# ES_Daisy_Field_Rev4.net
KiCad netlist of a schematic drawn in EAGLE
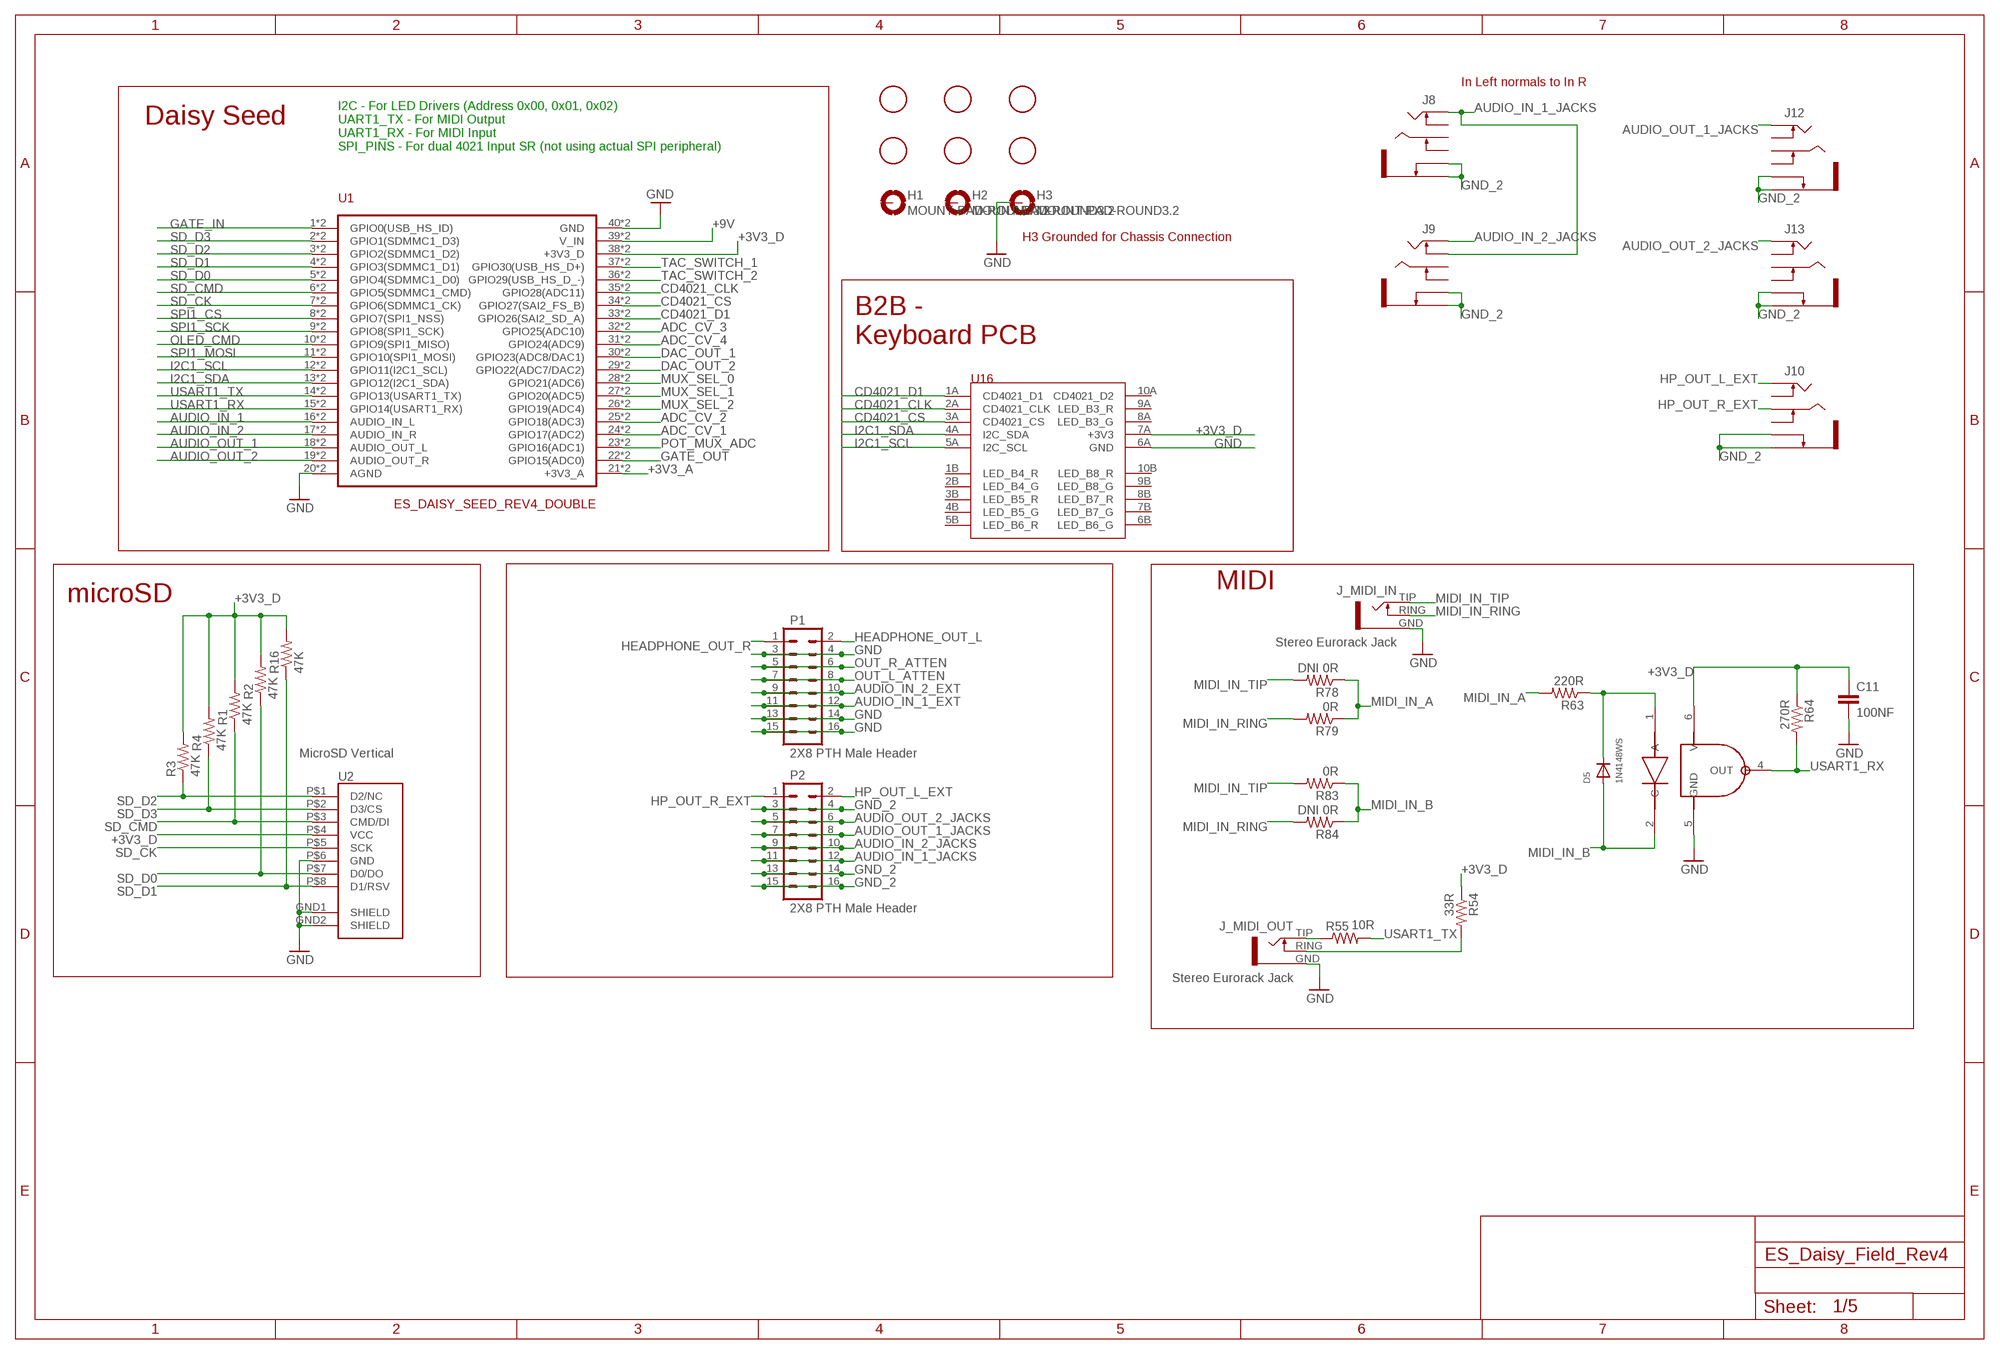
[diagram p0: schematic, sheet 1]
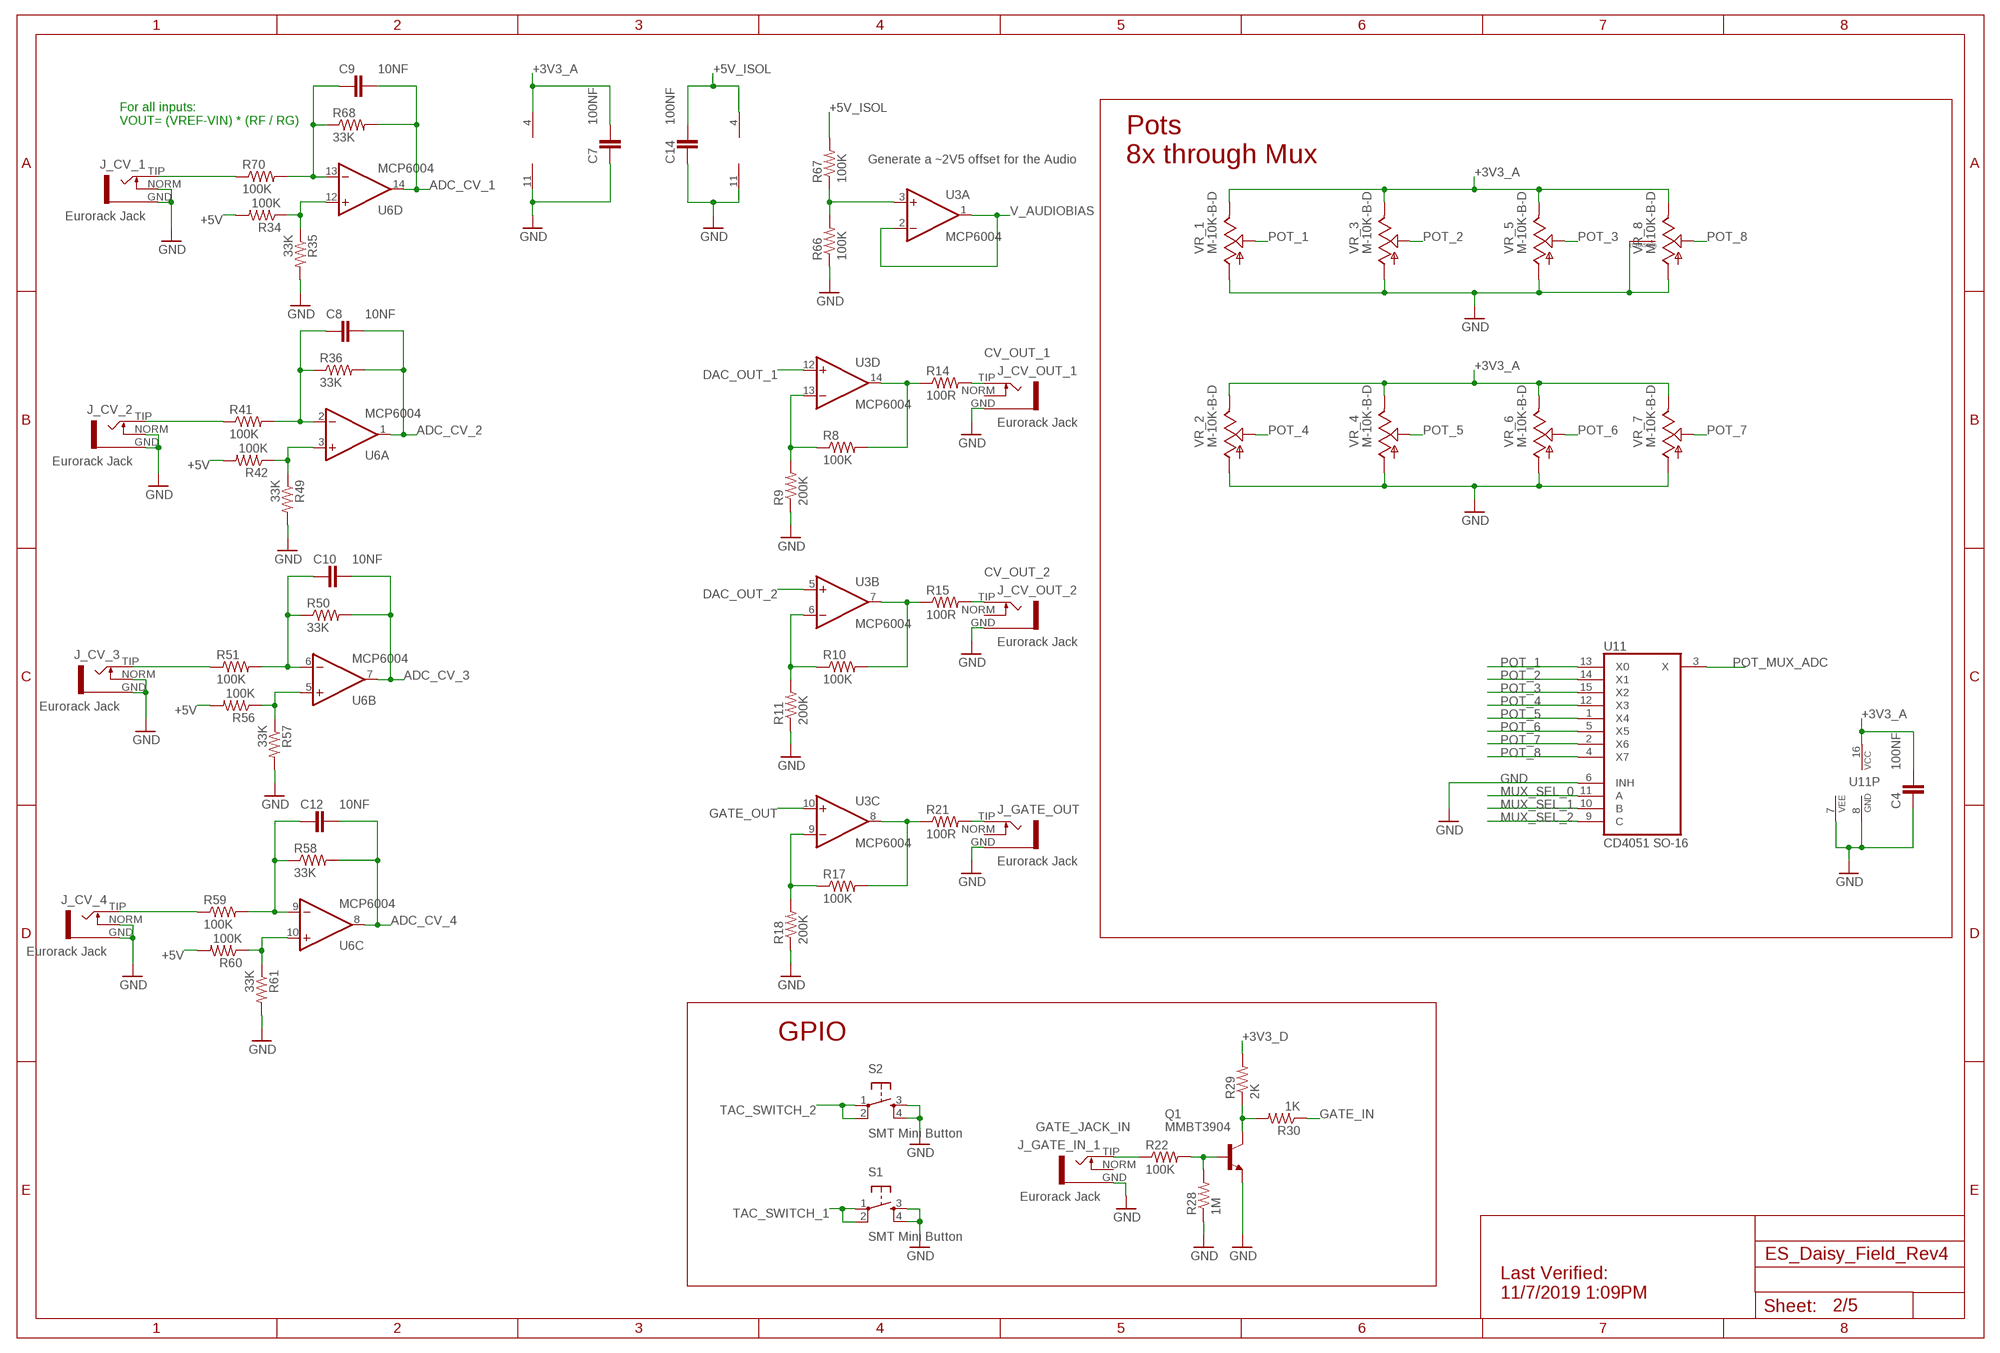
[diagram p1: schematic, sheet 2]
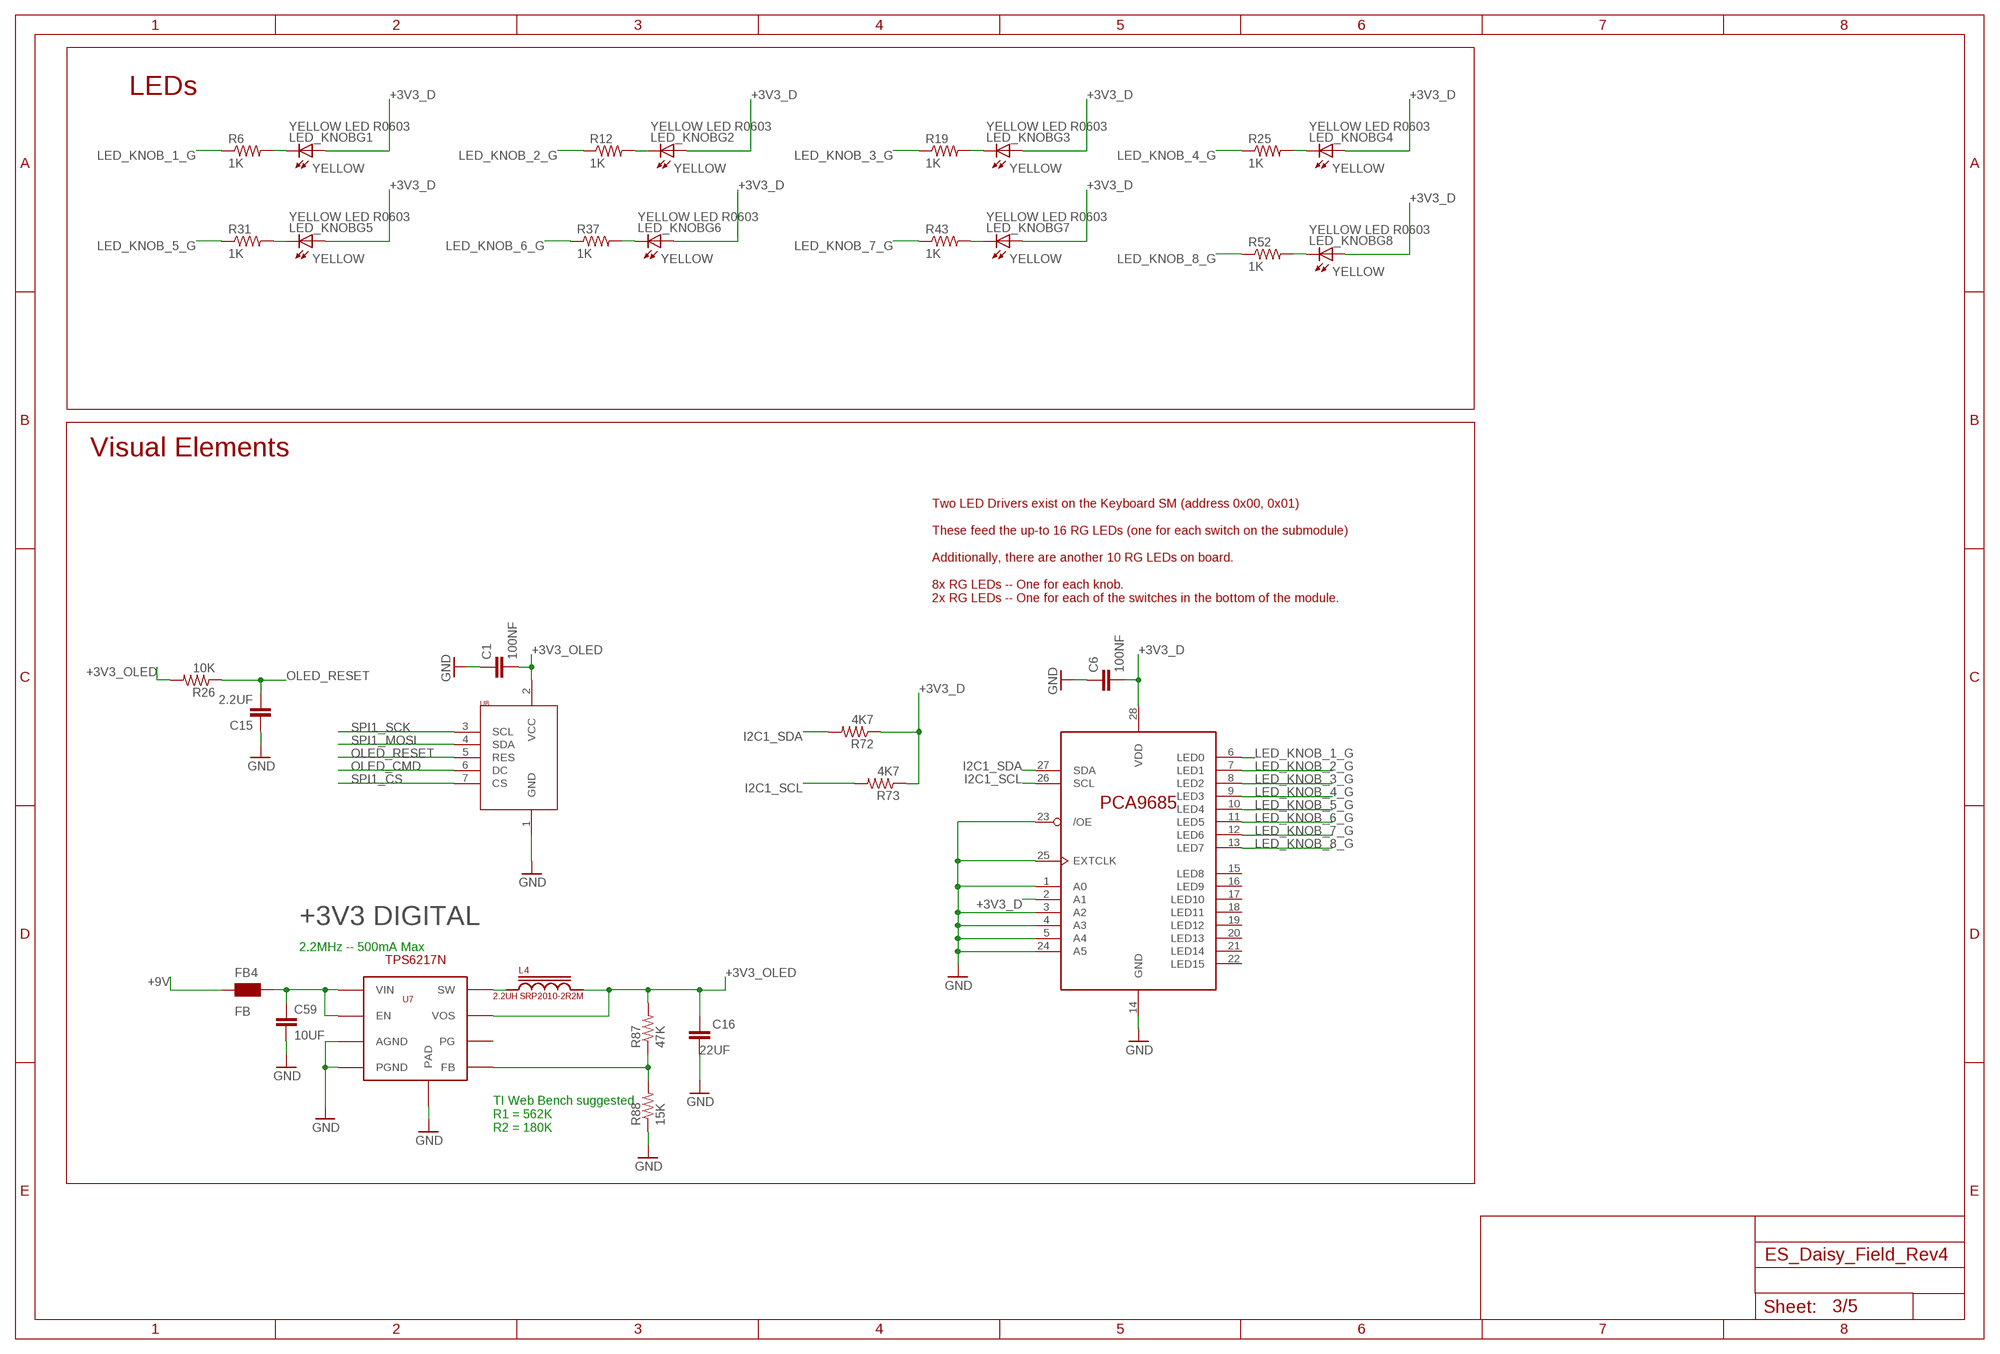
[diagram p2: schematic, sheet 3]
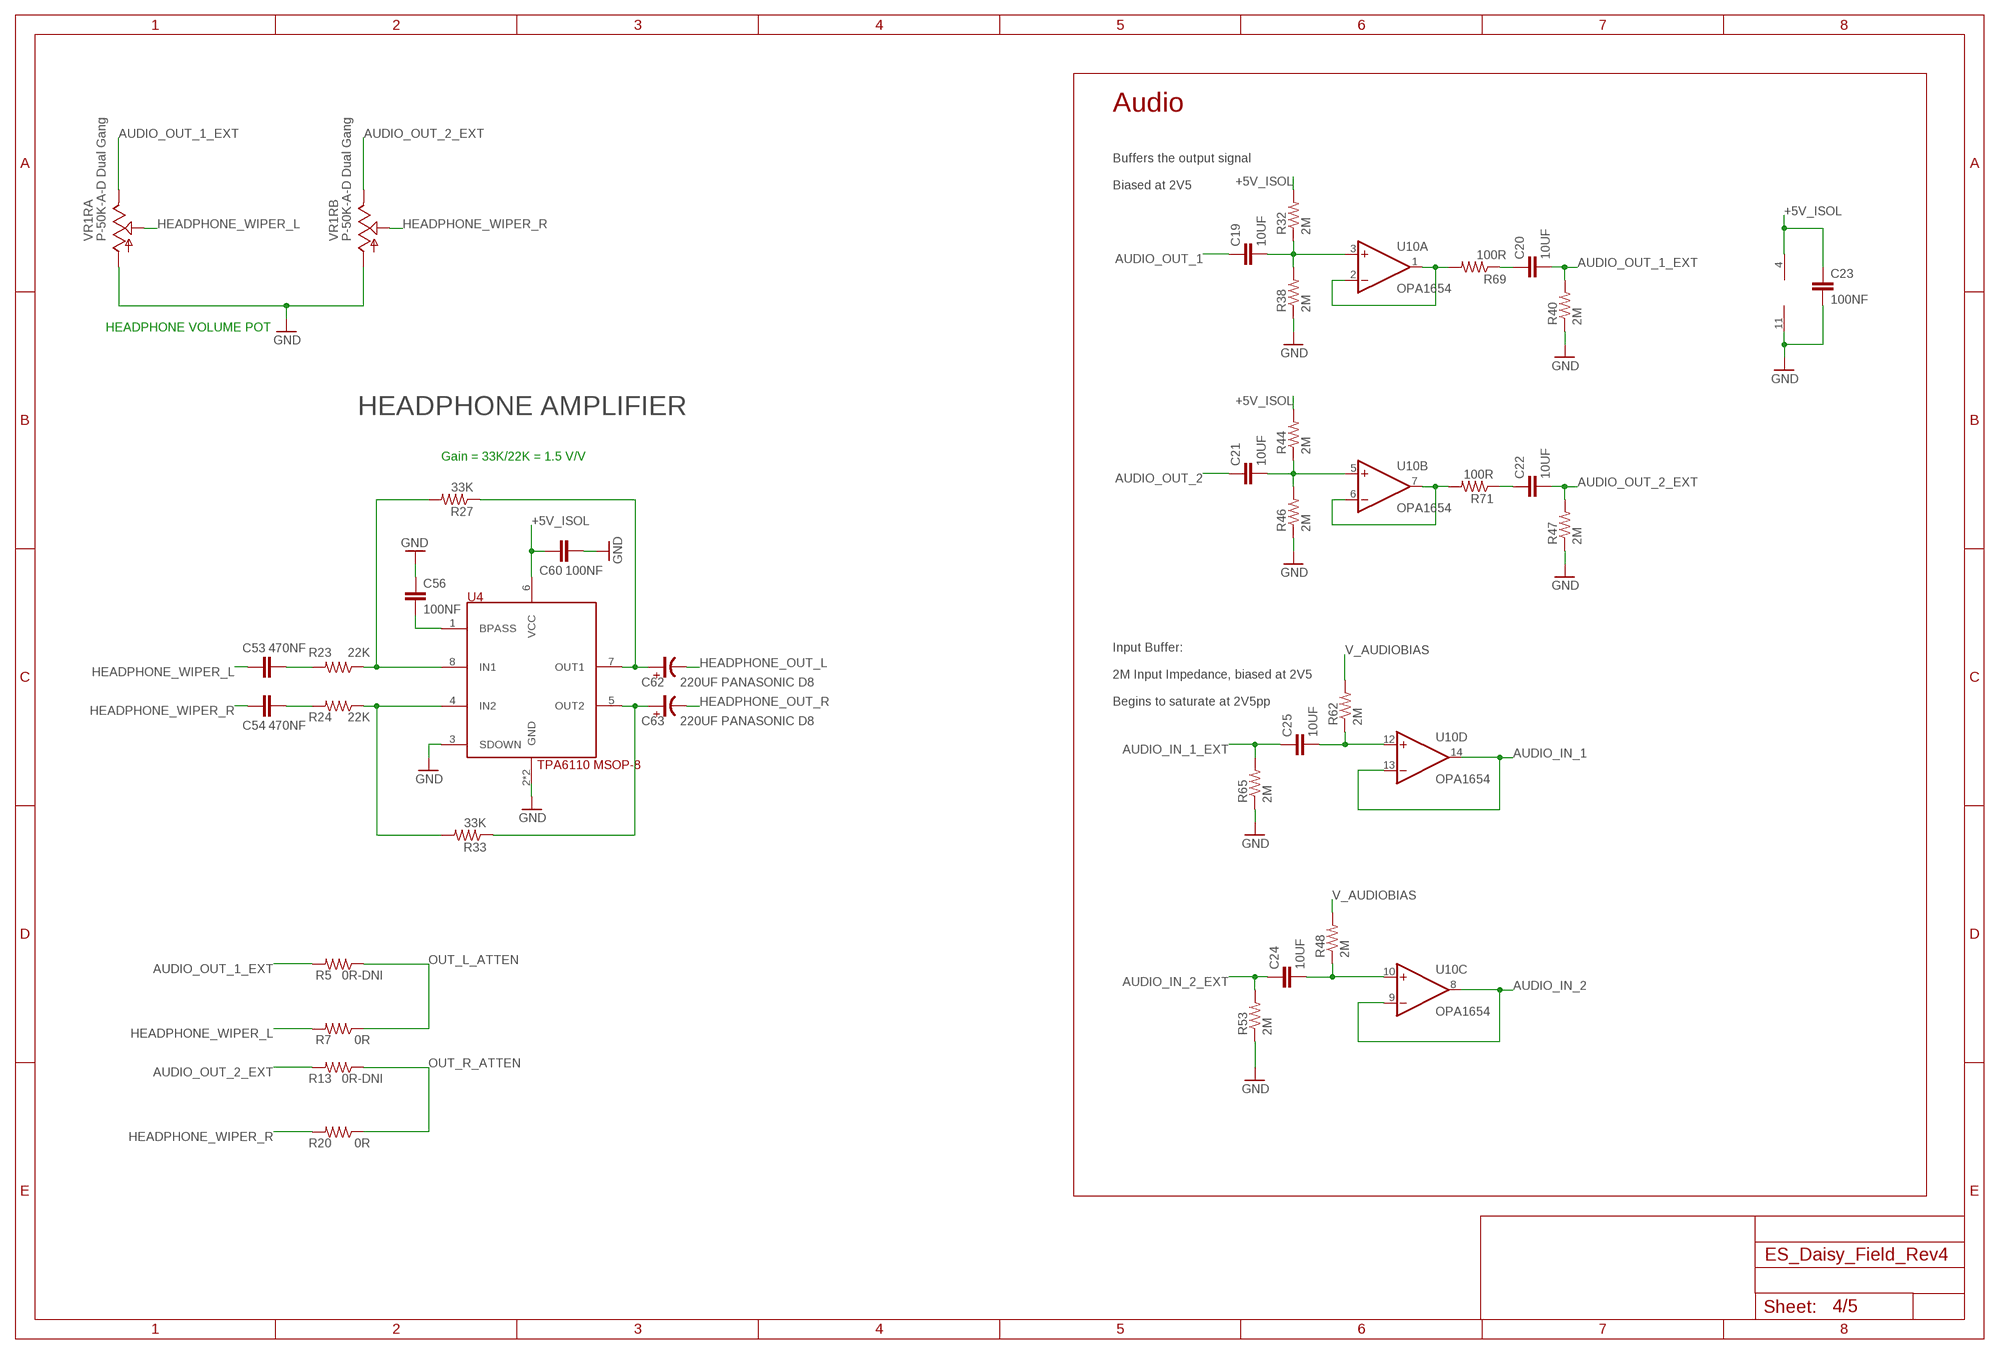
[diagram p3: schematic, sheet 4]
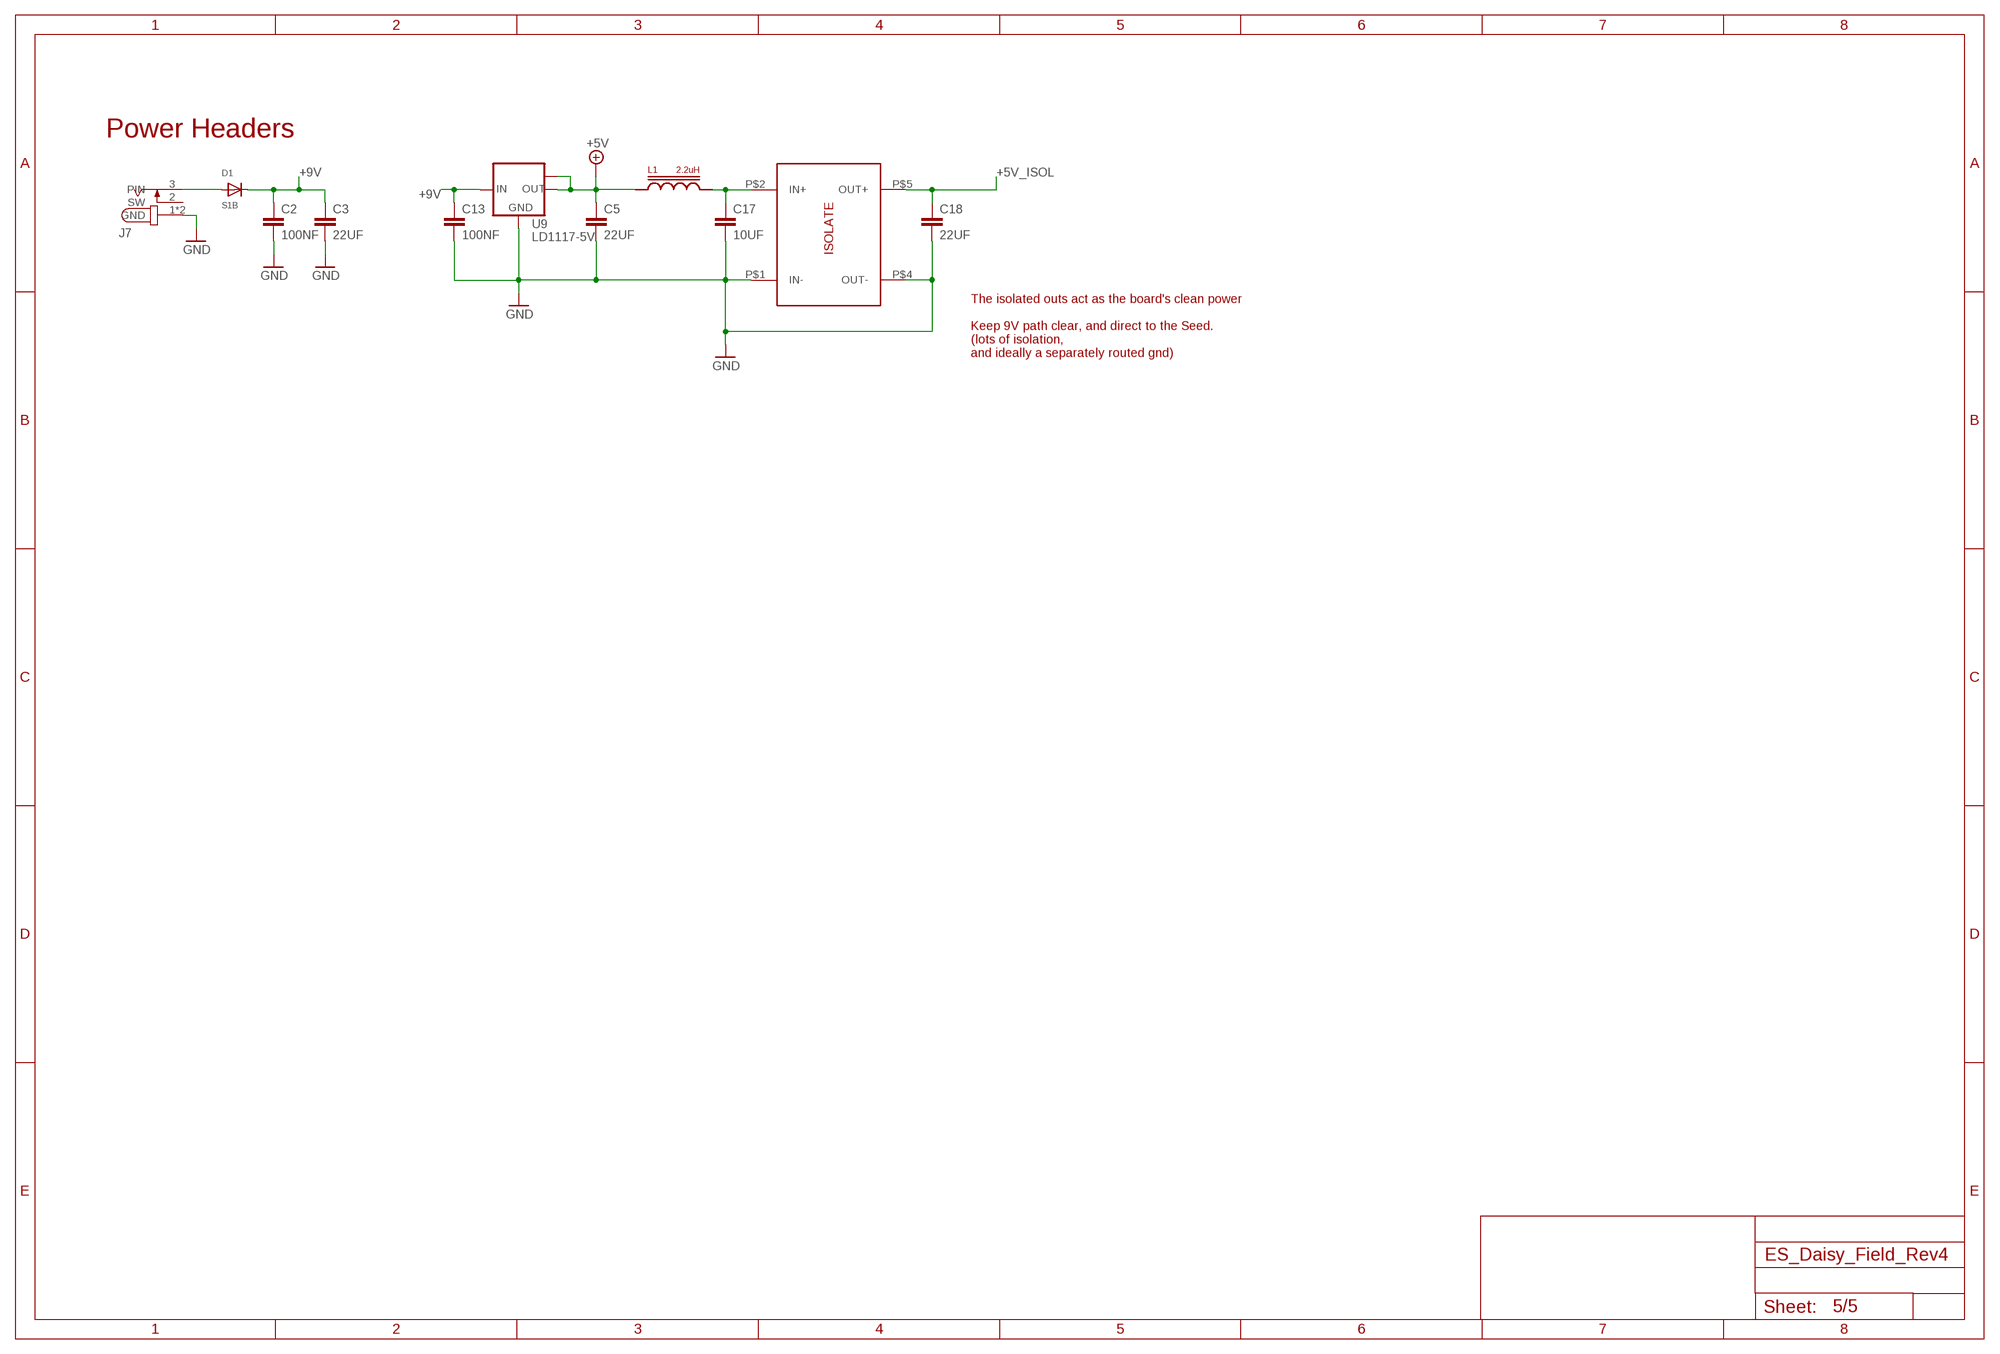
[diagram p4: schematic, sheet 5]

(export (version "E")
  (design (tool "Eeschema 10.0.6"))
  (components
    (comp (ref "C11")
      (value "100NF")
      (footprint "eagle-import:C0603")
      (libsource (lib "eagle-import") (part "C-EUC0603"))
    )
    (comp (ref "D5")
      (value "1N4148WS")
      (footprint "eagle-import:SOD-323F")
      (libsource (lib "eagle-import") (part "DIODE_SOD-323F"))
    )
    (comp (ref "FD1")
      (value "FIDUCIAL")
      (footprint "eagle-import:FIDUCIAL_1MM")
      (libsource (lib "eagle-import") (part "FIDUCIAL"))
    )
    (comp (ref "FD2")
      (value "FIDUCIAL")
      (footprint "eagle-import:FIDUCIAL_1MM")
      (libsource (lib "eagle-import") (part "FIDUCIAL"))
    )
    (comp (ref "FD3")
      (value "FIDUCIAL")
      (footprint "eagle-import:FIDUCIAL_1MM")
      (libsource (lib "eagle-import") (part "FIDUCIAL"))
    )
    (comp (ref "FD4")
      (value "FIDUCIAL")
      (footprint "eagle-import:FIDUCIAL_1MM")
      (libsource (lib "eagle-import") (part "FIDUCIAL"))
    )
    (comp (ref "FD5")
      (value "FIDUCIAL")
      (footprint "eagle-import:FIDUCIAL_1MM")
      (libsource (lib "eagle-import") (part "FIDUCIAL"))
    )
    (comp (ref "FD6")
      (value "FIDUCIAL")
      (footprint "eagle-import:FIDUCIAL_1MM")
      (libsource (lib "eagle-import") (part "FIDUCIAL"))
    )
    (comp (ref "H1")
      (value "MOUNT-PAD-ROUND3.2")
      (footprint "eagle-import:32-PAD")
      (libsource (lib "eagle-import") (part "MOUNT-PAD-ROUND3.2"))
    )
    (comp (ref "H2")
      (value "MOUNT-PAD-ROUND3.2")
      (footprint "eagle-import:32-PAD")
      (libsource (lib "eagle-import") (part "MOUNT-PAD-ROUND3.2"))
    )
    (comp (ref "H3")
      (value "MOUNT-PAD-ROUND3.2")
      (footprint "eagle-import:32-PAD")
      (libsource (lib "eagle-import") (part "MOUNT-PAD-ROUND3.2"))
    )
    (comp (ref "J8")
      (value "PTH Switching Stereo Guitar Jack")
      (footprint "eagle-import:WQP-PJ6110")
      (libsource (lib "eagle-import") (part "JACK_TRS_SWITCHING_WQP-PJ6110"))
    )
    (comp (ref "J9")
      (value "PTH Switching Stereo Guitar Jack")
      (footprint "eagle-import:WQP-PJ6110")
      (libsource (lib "eagle-import") (part "JACK_TRS_SWITCHING_WQP-PJ6110"))
    )
    (comp (ref "J10")
      (value "PTH Switching Stereo Guitar Jack")
      (footprint "eagle-import:WQP-PJ6110")
      (libsource (lib "eagle-import") (part "JACK_TRS_SWITCHING_WQP-PJ6110"))
    )
    (comp (ref "J12")
      (value "PTH Switching Stereo Guitar Jack")
      (footprint "eagle-import:WQP-PJ6110")
      (libsource (lib "eagle-import") (part "JACK_TRS_SWITCHING_WQP-PJ6110"))
    )
    (comp (ref "J13")
      (value "PTH Switching Stereo Guitar Jack")
      (footprint "eagle-import:WQP-PJ6110")
      (libsource (lib "eagle-import") (part "JACK_TRS_SWITCHING_WQP-PJ6110"))
    )
    (comp (ref "J_MIDI_IN")
      (value "Stereo Eurorack Jack")
      (footprint "eagle-import:STEREO_JACK_3.5MM")
      (libsource (lib "eagle-import") (part "STEREO_JACK"))
    )
    (comp (ref "J_MIDI_OUT")
      (value "Stereo Eurorack Jack")
      (footprint "eagle-import:STEREO_JACK_3.5MM")
      (libsource (lib "eagle-import") (part "STEREO_JACK"))
    )
    (comp (ref "P1")
      (value "2X8 PTH Male Header")
      (footprint "eagle-import:2X8_LOCK")
      (libsource (lib "eagle-import") (part "M08X2?_LOCK_SILK"))
    )
    (comp (ref "P2")
      (value "2X8 PTH Male Header")
      (footprint "eagle-import:2X8_LOCK")
      (libsource (lib "eagle-import") (part "M08X2?_LOCK_SILK"))
    )
    (comp (ref "R1")
      (value "47K")
      (footprint "eagle-import:R0603")
      (libsource (lib "eagle-import") (part "R-US_R0603"))
    )
    (comp (ref "R2")
      (value "47K")
      (footprint "eagle-import:R0603")
      (libsource (lib "eagle-import") (part "R-US_R0603"))
    )
    (comp (ref "R3")
      (value "47K")
      (footprint "eagle-import:R0603")
      (libsource (lib "eagle-import") (part "R-US_R0603"))
    )
    (comp (ref "R4")
      (value "47K")
      (footprint "eagle-import:R0603")
      (libsource (lib "eagle-import") (part "R-US_R0603"))
    )
    (comp (ref "R16")
      (value "47K")
      (footprint "eagle-import:R0603")
      (libsource (lib "eagle-import") (part "R-US_R0603"))
    )
    (comp (ref "R54")
      (value "33R")
      (footprint "eagle-import:R0603")
      (libsource (lib "eagle-import") (part "R-US_R0603"))
    )
    (comp (ref "R55")
      (value "10R")
      (footprint "eagle-import:R0603")
      (libsource (lib "eagle-import") (part "R-US_R0603"))
    )
    (comp (ref "R63")
      (value "220R")
      (footprint "eagle-import:R0603")
      (libsource (lib "eagle-import") (part "R-US_R0603"))
    )
    (comp (ref "R64")
      (value "270R")
      (footprint "eagle-import:R0603")
      (libsource (lib "eagle-import") (part "R-US_R0603"))
    )
    (comp (ref "R78")
      (value "DNI 0R")
      (footprint "eagle-import:R0603")
      (libsource (lib "eagle-import") (part "R-US_R0603"))
    )
    (comp (ref "R79")
      (value "0R")
      (footprint "eagle-import:R0603")
      (libsource (lib "eagle-import") (part "R-US_R0603"))
    )
    (comp (ref "R83")
      (value "0R")
      (footprint "eagle-import:R0603")
      (libsource (lib "eagle-import") (part "R-US_R0603"))
    )
    (comp (ref "R84")
      (value "DNI 0R")
      (footprint "eagle-import:R0603")
      (libsource (lib "eagle-import") (part "R-US_R0603"))
    )
    (comp (ref "U1")
      (value "ES_DAISY_SEED_REV4_DOUBLE")
      (footprint "eagle-import:ES_DAISY_SEED_DOUBLE")
      (libsource (lib "eagle-import") (part "ES_DAISY_SEED_REV4_DOUBLE"))
    )
    (comp (ref "U2")
      (value "MicroSD Vertical")
      (footprint "eagle-import:VERT_MICROSD_CENTERED")
      (libsource (lib "eagle-import") (part "MICRO_SD_CARDCENTERED"))
    )
    (comp (ref "U15")
      (value "OPTO ISOLATOR")
      (footprint "eagle-import:DIL06_GULLWING")
      (fields (field (name "MPN") "H11L1SR2M"))
      (libsource (lib "eagle-import") (part "OPTOISOLATOR_H11L1M"))
    )
    (comp (ref "U16")
      (value "ES_KEYBOARD_SM_REV2_ALIGNED")
      (footprint "eagle-import:ES_KEYBOARD_SM_REV2_ALIGNED")
      (libsource (lib "eagle-import") (part "ES_KEYBOARD_SM_REV2_ALIGNED"))
    )
    (comp (ref "C1")
      (value "100NF")
      (footprint "eagle-import:C0603")
      (libsource (lib "eagle-import") (part "C-EUC0603"))
    )
    (comp (ref "C6")
      (value "100NF")
      (footprint "eagle-import:C0603")
      (libsource (lib "eagle-import") (part "C-EUC0603"))
    )
    (comp (ref "C15")
      (value "2.2UF")
      (footprint "eagle-import:C0603")
      (libsource (lib "eagle-import") (part "C-EUC0603"))
    )
    (comp (ref "C16")
      (value "22UF")
      (footprint "eagle-import:C1206")
      (libsource (lib "eagle-import") (part "C-EUC1206"))
    )
    (comp (ref "C59")
      (value "10UF")
      (footprint "eagle-import:C0805")
      (libsource (lib "eagle-import") (part "C-EUC0805"))
    )
    (comp (ref "FB4")
      (value "FB")
      (footprint "eagle-import:WUERTH-ELEKTRONIK_0603")
      (fields (field (name "MPN") "MI0603J601R-10"))
      (libsource (lib "eagle-import") (part "FERRITE_BEAD_0603"))
    )
    (comp (ref "L4")
      (value "2.2UH SRP2010-2R2M")
      (footprint "eagle-import:BOURNS_SRP2010")
      (libsource (lib "eagle-import") (part "INDUCTORS"))
    )
    (comp (ref "LED_KNOBG1")
      (value "YELLOW LED R0603")
      (footprint "eagle-import:DIODE_0603")
      (fields (field (name "COLOR") "YELLOW") (field (name "MPN") "APT1608LSYCK/J3-PRV"))
      (libsource (lib "eagle-import") (part "LED_0603_YELLOW"))
    )
    (comp (ref "LED_KNOBG2")
      (value "YELLOW LED R0603")
      (footprint "eagle-import:DIODE_0603")
      (fields (field (name "COLOR") "YELLOW") (field (name "MPN") "APT1608LSYCK/J3-PRV"))
      (libsource (lib "eagle-import") (part "LED_0603_YELLOW"))
    )
    (comp (ref "LED_KNOBG3")
      (value "YELLOW LED R0603")
      (footprint "eagle-import:DIODE_0603")
      (fields (field (name "COLOR") "YELLOW") (field (name "MPN") "APT1608LSYCK/J3-PRV"))
      (libsource (lib "eagle-import") (part "LED_0603_YELLOW"))
    )
    (comp (ref "LED_KNOBG4")
      (value "YELLOW LED R0603")
      (footprint "eagle-import:DIODE_0603")
      (fields (field (name "COLOR") "YELLOW") (field (name "MPN") "APT1608LSYCK/J3-PRV"))
      (libsource (lib "eagle-import") (part "LED_0603_YELLOW"))
    )
    (comp (ref "LED_KNOBG5")
      (value "YELLOW LED R0603")
      (footprint "eagle-import:DIODE_0603")
      (fields (field (name "COLOR") "YELLOW") (field (name "MPN") "APT1608LSYCK/J3-PRV"))
      (libsource (lib "eagle-import") (part "LED_0603_YELLOW"))
    )
    (comp (ref "LED_KNOBG6")
      (value "YELLOW LED R0603")
      (footprint "eagle-import:DIODE_0603")
      (fields (field (name "COLOR") "YELLOW") (field (name "MPN") "APT1608LSYCK/J3-PRV"))
      (libsource (lib "eagle-import") (part "LED_0603_YELLOW"))
    )
    (comp (ref "LED_KNOBG7")
      (value "YELLOW LED R0603")
      (footprint "eagle-import:DIODE_0603")
      (fields (field (name "COLOR") "YELLOW") (field (name "MPN") "APT1608LSYCK/J3-PRV"))
      (libsource (lib "eagle-import") (part "LED_0603_YELLOW"))
    )
    (comp (ref "LED_KNOBG8")
      (value "YELLOW LED R0603")
      (footprint "eagle-import:DIODE_0603")
      (fields (field (name "COLOR") "YELLOW") (field (name "MPN") "APT1608LSYCK/J3-PRV"))
      (libsource (lib "eagle-import") (part "LED_0603_YELLOW"))
    )
    (comp (ref "R6")
      (value "1K")
      (footprint "eagle-import:R0603")
      (libsource (lib "eagle-import") (part "R-US_R0603"))
    )
    (comp (ref "R12")
      (value "1K")
      (footprint "eagle-import:R0603")
      (libsource (lib "eagle-import") (part "R-US_R0603"))
    )
    (comp (ref "R19")
      (value "1K")
      (footprint "eagle-import:R0603")
      (libsource (lib "eagle-import") (part "R-US_R0603"))
    )
    (comp (ref "R25")
      (value "1K")
      (footprint "eagle-import:R0603")
      (libsource (lib "eagle-import") (part "R-US_R0603"))
    )
    (comp (ref "R26")
      (value "10K")
      (footprint "eagle-import:R0603")
      (libsource (lib "eagle-import") (part "R-US_R0603"))
    )
    (comp (ref "R31")
      (value "1K")
      (footprint "eagle-import:R0603")
      (libsource (lib "eagle-import") (part "R-US_R0603"))
    )
    (comp (ref "R37")
      (value "1K")
      (footprint "eagle-import:R0603")
      (libsource (lib "eagle-import") (part "R-US_R0603"))
    )
    (comp (ref "R43")
      (value "1K")
      (footprint "eagle-import:R0603")
      (libsource (lib "eagle-import") (part "R-US_R0603"))
    )
    (comp (ref "R52")
      (value "1K")
      (footprint "eagle-import:R0603")
      (libsource (lib "eagle-import") (part "R-US_R0603"))
    )
    (comp (ref "R72")
      (value "4K7")
      (footprint "eagle-import:R0603")
      (libsource (lib "eagle-import") (part "R-US_R0603"))
    )
    (comp (ref "R73")
      (value "4K7")
      (footprint "eagle-import:R0603")
      (libsource (lib "eagle-import") (part "R-US_R0603"))
    )
    (comp (ref "R87")
      (value "47K")
      (footprint "eagle-import:R0603")
      (libsource (lib "eagle-import") (part "R-US_R0603"))
    )
    (comp (ref "R88")
      (value "15K")
      (footprint "eagle-import:R0603")
      (libsource (lib "eagle-import") (part "R-US_R0603"))
    )
    (comp (ref "U5")
      (value "PCA9685 TSSOP-28")
      (footprint "eagle-import:TSSOP-28")
      (fields (field (name "MPN") "PCA9685PW,118"))
      (libsource (lib "eagle-import") (part "PCA9685PW"))
    )
    (comp (ref "U7")
      (value "TPS62170 WSON-8")
      (footprint "eagle-import:WSON-8")
      (fields (field (name "MPN") "TPS62170"))
      (libsource (lib "eagle-import") (part "TPS6217N"))
    )
    (comp (ref "U8")
      (value "OLED_DISPLAY")
      (footprint "eagle-import:ER-OLEDM015-2")
      (fields (field (name "MPN") "ER-OLEDM015-2W-SPI-I2C"))
      (libsource (lib "eagle-import") (part "OLED_DISPLAY"))
    )
    (comp (ref "C2")
      (value "100NF")
      (footprint "eagle-import:C0603")
      (libsource (lib "eagle-import") (part "C-EUC0603"))
    )
    (comp (ref "C3")
      (value "22UF")
      (footprint "eagle-import:C1206")
      (libsource (lib "eagle-import") (part "C-EUC1206"))
    )
    (comp (ref "C5")
      (value "22UF")
      (footprint "eagle-import:C0805")
      (libsource (lib "eagle-import") (part "C-EUC0805"))
    )
    (comp (ref "C13")
      (value "100NF")
      (footprint "eagle-import:C0603")
      (libsource (lib "eagle-import") (part "C-EUC0603"))
    )
    (comp (ref "C17")
      (value "10UF")
      (footprint "eagle-import:C0805")
      (libsource (lib "eagle-import") (part "C-EUC0805"))
    )
    (comp (ref "C18")
      (value "22UF")
      (footprint "eagle-import:C1206")
      (libsource (lib "eagle-import") (part "C-EUC1206"))
    )
    (comp (ref "D1")
      (value "S1B")
      (footprint "eagle-import:SMADIODE")
      (libsource (lib "eagle-import") (part "S1B"))
    )
    (comp (ref "J7")
      (value "SMT GUITAR DC JACK")
      (footprint "eagle-import:WQP-DC0500")
      (libsource (lib "eagle-import") (part "GUITAR_DC_JACK"))
    )
    (comp (ref "L1")
      (value "2.2uH")
      (footprint "eagle-import:BOURNS_SRP2010")
      (libsource (lib "eagle-import") (part "INDUCTORS"))
    )
    (comp (ref "U$4")
      (value "POWER_ISOLATE")
      (footprint "eagle-import:XP_POWER_ISEXXXXA")
      (fields (field (name "MPN") "ISE2405A"))
      (libsource (lib "eagle-import") (part "POWER_ISOLATE"))
    )
    (comp (ref "U9")
      (value "LD1117-5V")
      (footprint "eagle-import:SOT223")
      (fields (field (name "MPN") "LD1117S50CTR"))
      (libsource (lib "eagle-import") (part "LD1117-5V"))
    )
    (comp (ref "C19")
      (value "10UF")
      (footprint "eagle-import:C0805")
      (libsource (lib "eagle-import") (part "C-EUC0805"))
    )
    (comp (ref "C20")
      (value "10UF")
      (footprint "eagle-import:C0805")
      (libsource (lib "eagle-import") (part "C-EUC0805"))
    )
    (comp (ref "C21")
      (value "10UF")
      (footprint "eagle-import:C0805")
      (libsource (lib "eagle-import") (part "C-EUC0805"))
    )
    (comp (ref "C22")
      (value "10UF")
      (footprint "eagle-import:C0805")
      (libsource (lib "eagle-import") (part "C-EUC0805"))
    )
    (comp (ref "C23")
      (value "100NF")
      (footprint "eagle-import:C0603")
      (libsource (lib "eagle-import") (part "C-EUC0603"))
    )
    (comp (ref "C24")
      (value "10UF")
      (footprint "eagle-import:C0805")
      (libsource (lib "eagle-import") (part "C-EUC0805"))
    )
    (comp (ref "C25")
      (value "10UF")
      (footprint "eagle-import:C0805")
      (libsource (lib "eagle-import") (part "C-EUC0805"))
    )
    (comp (ref "C53")
      (value "470NF")
      (footprint "eagle-import:C0603")
      (libsource (lib "eagle-import") (part "C-EUC0603"))
    )
    (comp (ref "C54")
      (value "470NF")
      (footprint "eagle-import:C0603")
      (libsource (lib "eagle-import") (part "C-EUC0603"))
    )
    (comp (ref "C56")
      (value "100NF")
      (footprint "eagle-import:C0603")
      (libsource (lib "eagle-import") (part "C-EUC0603"))
    )
    (comp (ref "C60")
      (value "100NF")
      (footprint "eagle-import:C0603")
      (libsource (lib "eagle-import") (part "C-EUC0603"))
    )
    (comp (ref "C62")
      (value "220UF PANASONIC D8")
      (footprint "eagle-import:PANASONIC_D")
      (libsource (lib "eagle-import") (part "C-EU-POL_D"))
    )
    (comp (ref "C63")
      (value "220UF PANASONIC D8")
      (footprint "eagle-import:PANASONIC_D")
      (libsource (lib "eagle-import") (part "C-EU-POL_D"))
    )
    (comp (ref "R5")
      (value "0R-DNI")
      (footprint "eagle-import:R0603")
      (libsource (lib "eagle-import") (part "R-US_R0603"))
    )
    (comp (ref "R7")
      (value "0R")
      (footprint "eagle-import:R0603")
      (libsource (lib "eagle-import") (part "R-US_R0603"))
    )
    (comp (ref "R13")
      (value "0R-DNI")
      (footprint "eagle-import:R0603")
      (libsource (lib "eagle-import") (part "R-US_R0603"))
    )
    (comp (ref "R20")
      (value "0R")
      (footprint "eagle-import:R0603")
      (libsource (lib "eagle-import") (part "R-US_R0603"))
    )
    (comp (ref "R23")
      (value "22K")
      (footprint "eagle-import:R0603")
      (libsource (lib "eagle-import") (part "R-US_R0603"))
    )
    (comp (ref "R24")
      (value "22K")
      (footprint "eagle-import:R0603")
      (libsource (lib "eagle-import") (part "R-US_R0603"))
    )
    (comp (ref "R27")
      (value "33K")
      (footprint "eagle-import:R0603")
      (libsource (lib "eagle-import") (part "R-US_R0603"))
    )
    (comp (ref "R32")
      (value "2M")
      (footprint "eagle-import:R0603")
      (libsource (lib "eagle-import") (part "R-US_R0603"))
    )
    (comp (ref "R33")
      (value "33K")
      (footprint "eagle-import:R0603")
      (libsource (lib "eagle-import") (part "R-US_R0603"))
    )
    (comp (ref "R38")
      (value "2M")
      (footprint "eagle-import:R0603")
      (libsource (lib "eagle-import") (part "R-US_R0603"))
    )
    (comp (ref "R40")
      (value "2M")
      (footprint "eagle-import:R0603")
      (libsource (lib "eagle-import") (part "R-US_R0603"))
    )
    (comp (ref "R44")
      (value "2M")
      (footprint "eagle-import:R0603")
      (libsource (lib "eagle-import") (part "R-US_R0603"))
    )
    (comp (ref "R46")
      (value "2M")
      (footprint "eagle-import:R0603")
      (libsource (lib "eagle-import") (part "R-US_R0603"))
    )
    (comp (ref "R47")
      (value "2M")
      (footprint "eagle-import:R0603")
      (libsource (lib "eagle-import") (part "R-US_R0603"))
    )
    (comp (ref "R48")
      (value "2M")
      (footprint "eagle-import:R0603")
      (libsource (lib "eagle-import") (part "R-US_R0603"))
    )
    (comp (ref "R53")
      (value "2M")
      (footprint "eagle-import:R0603")
      (libsource (lib "eagle-import") (part "R-US_R0603"))
    )
    (comp (ref "R62")
      (value "2M")
      (footprint "eagle-import:R0603")
      (libsource (lib "eagle-import") (part "R-US_R0603"))
    )
    (comp (ref "R65")
      (value "2M")
      (footprint "eagle-import:R0603")
      (libsource (lib "eagle-import") (part "R-US_R0603"))
    )
    (comp (ref "R69")
      (value "100R")
      (footprint "eagle-import:R0603")
      (libsource (lib "eagle-import") (part "R-US_R0603"))
    )
    (comp (ref "R71")
      (value "100R")
      (footprint "eagle-import:R0603")
      (libsource (lib "eagle-import") (part "R-US_R0603"))
    )
    (comp (ref "U4")
      (value "TPA6110 MSOP-8")
      (footprint "eagle-import:MSOP_8_PWRPAD")
      (libsource (lib "eagle-import") (part "TPA6110MSOP"))
    )
    (comp (ref "U10")
      (value "OPA1654")
      (footprint "eagle-import:TSSOP-14")
      (libsource (lib "eagle-import") (part "OPA1654_TSSOP-14"))
    )
    (comp (ref "VR1")
      (value "P-50K-A-D Dual Gang")
      (footprint "eagle-import:BOURNS_PTV112_SILK")
      (libsource (lib "eagle-import") (part "POT_DUAL_GANG"))
    )
    (comp (ref "C4")
      (value "100NF")
      (footprint "eagle-import:C0603")
      (libsource (lib "eagle-import") (part "C-EUC0603"))
    )
    (comp (ref "C7")
      (value "100NF")
      (footprint "eagle-import:C0603")
      (libsource (lib "eagle-import") (part "C-EUC0603"))
    )
    (comp (ref "C8")
      (value "10NF")
      (footprint "eagle-import:C0603")
      (libsource (lib "eagle-import") (part "C-EUC0603"))
    )
    (comp (ref "C9")
      (value "10NF")
      (footprint "eagle-import:C0603")
      (libsource (lib "eagle-import") (part "C-EUC0603"))
    )
    (comp (ref "C10")
      (value "10NF")
      (footprint "eagle-import:C0603")
      (libsource (lib "eagle-import") (part "C-EUC0603"))
    )
    (comp (ref "C12")
      (value "10NF")
      (footprint "eagle-import:C0603")
      (libsource (lib "eagle-import") (part "C-EUC0603"))
    )
    (comp (ref "C14")
      (value "100NF")
      (footprint "eagle-import:C0603")
      (libsource (lib "eagle-import") (part "C-EUC0603"))
    )
    (comp (ref "J_CV_1")
      (value "Eurorack Jack")
      (footprint "eagle-import:S_JACK")
      (libsource (lib "eagle-import") (part "EURO_JACK"))
    )
    (comp (ref "J_CV_2")
      (value "Eurorack Jack")
      (footprint "eagle-import:S_JACK")
      (libsource (lib "eagle-import") (part "EURO_JACK"))
    )
    (comp (ref "J_CV_3")
      (value "Eurorack Jack")
      (footprint "eagle-import:S_JACK")
      (libsource (lib "eagle-import") (part "EURO_JACK"))
    )
    (comp (ref "J_CV_4")
      (value "Eurorack Jack")
      (footprint "eagle-import:S_JACK")
      (libsource (lib "eagle-import") (part "EURO_JACK"))
    )
    (comp (ref "J_CV_OUT_1")
      (value "Eurorack Jack")
      (footprint "eagle-import:S_JACK")
      (libsource (lib "eagle-import") (part "EURO_JACK"))
    )
    (comp (ref "J_CV_OUT_2")
      (value "Eurorack Jack")
      (footprint "eagle-import:S_JACK")
      (libsource (lib "eagle-import") (part "EURO_JACK"))
    )
    (comp (ref "J_GATE_IN_1")
      (value "Eurorack Jack")
      (footprint "eagle-import:S_JACK")
      (libsource (lib "eagle-import") (part "EURO_JACK"))
    )
    (comp (ref "J_GATE_OUT")
      (value "Eurorack Jack")
      (footprint "eagle-import:S_JACK")
      (libsource (lib "eagle-import") (part "EURO_JACK"))
    )
    (comp (ref "Q1")
      (value "MMBT3904")
      (footprint "eagle-import:SOT23-BEC")
      (libsource (lib "eagle-import") (part "NPNSOT23-BEC"))
    )
    (comp (ref "R8")
      (value "100K")
      (footprint "eagle-import:R0603")
      (libsource (lib "eagle-import") (part "R-US_R0603"))
    )
    (comp (ref "R9")
      (value "200K")
      (footprint "eagle-import:R0603")
      (libsource (lib "eagle-import") (part "R-US_R0603"))
    )
    (comp (ref "R10")
      (value "100K")
      (footprint "eagle-import:R0603")
      (libsource (lib "eagle-import") (part "R-US_R0603"))
    )
    (comp (ref "R11")
      (value "200K")
      (footprint "eagle-import:R0603")
      (libsource (lib "eagle-import") (part "R-US_R0603"))
    )
    (comp (ref "R14")
      (value "100R")
      (footprint "eagle-import:R0603")
      (libsource (lib "eagle-import") (part "R-US_R0603"))
    )
    (comp (ref "R15")
      (value "100R")
      (footprint "eagle-import:R0603")
      (libsource (lib "eagle-import") (part "R-US_R0603"))
    )
    (comp (ref "R17")
      (value "100K")
      (footprint "eagle-import:R0603")
      (libsource (lib "eagle-import") (part "R-US_R0603"))
    )
    (comp (ref "R18")
      (value "200K")
      (footprint "eagle-import:R0603")
      (libsource (lib "eagle-import") (part "R-US_R0603"))
    )
    (comp (ref "R21")
      (value "100R")
      (footprint "eagle-import:R0603")
      (libsource (lib "eagle-import") (part "R-US_R0603"))
    )
    (comp (ref "R22")
      (value "100K")
      (footprint "eagle-import:R0603")
      (libsource (lib "eagle-import") (part "R-US_R0603"))
    )
    (comp (ref "R28")
      (value "1M")
      (footprint "eagle-import:R0603")
      (libsource (lib "eagle-import") (part "R-US_R0603"))
    )
    (comp (ref "R29")
      (value "2K")
      (footprint "eagle-import:R0603")
      (libsource (lib "eagle-import") (part "R-US_R0603"))
    )
    (comp (ref "R30")
      (value "1K")
      (footprint "eagle-import:R0603")
      (libsource (lib "eagle-import") (part "R-US_R0603"))
    )
    (comp (ref "R34")
      (value "100K")
      (footprint "eagle-import:R0603")
      (libsource (lib "eagle-import") (part "R-US_R0603"))
    )
    (comp (ref "R35")
      (value "33K")
      (footprint "eagle-import:R0603")
      (libsource (lib "eagle-import") (part "R-US_R0603"))
    )
    (comp (ref "R36")
      (value "33K")
      (footprint "eagle-import:R0603")
      (libsource (lib "eagle-import") (part "R-US_R0603"))
    )
    (comp (ref "R41")
      (value "100K")
      (footprint "eagle-import:R0603")
      (libsource (lib "eagle-import") (part "R-US_R0603"))
    )
    (comp (ref "R42")
      (value "100K")
      (footprint "eagle-import:R0603")
      (libsource (lib "eagle-import") (part "R-US_R0603"))
    )
    (comp (ref "R49")
      (value "33K")
      (footprint "eagle-import:R0603")
      (libsource (lib "eagle-import") (part "R-US_R0603"))
    )
    (comp (ref "R50")
      (value "33K")
      (footprint "eagle-import:R0603")
      (libsource (lib "eagle-import") (part "R-US_R0603"))
    )
    (comp (ref "R51")
      (value "100K")
      (footprint "eagle-import:R0603")
      (libsource (lib "eagle-import") (part "R-US_R0603"))
    )
    (comp (ref "R56")
      (value "100K")
      (footprint "eagle-import:R0603")
      (libsource (lib "eagle-import") (part "R-US_R0603"))
    )
    (comp (ref "R57")
      (value "33K")
      (footprint "eagle-import:R0603")
      (libsource (lib "eagle-import") (part "R-US_R0603"))
    )
    (comp (ref "R58")
      (value "33K")
      (footprint "eagle-import:R0603")
      (libsource (lib "eagle-import") (part "R-US_R0603"))
    )
    (comp (ref "R59")
      (value "100K")
      (footprint "eagle-import:R0603")
      (libsource (lib "eagle-import") (part "R-US_R0603"))
    )
    (comp (ref "R60")
      (value "100K")
      (footprint "eagle-import:R0603")
      (libsource (lib "eagle-import") (part "R-US_R0603"))
    )
    (comp (ref "R61")
      (value "33K")
      (footprint "eagle-import:R0603")
      (libsource (lib "eagle-import") (part "R-US_R0603"))
    )
    (comp (ref "R66")
      (value "100K")
      (footprint "eagle-import:R0603")
      (libsource (lib "eagle-import") (part "R-US_R0603"))
    )
    (comp (ref "R67")
      (value "100K")
      (footprint "eagle-import:R0603")
      (libsource (lib "eagle-import") (part "R-US_R0603"))
    )
    (comp (ref "R68")
      (value "33K")
      (footprint "eagle-import:R0603")
      (libsource (lib "eagle-import") (part "R-US_R0603"))
    )
    (comp (ref "R70")
      (value "100K")
      (footprint "eagle-import:R0603")
      (libsource (lib "eagle-import") (part "R-US_R0603"))
    )
    (comp (ref "S1")
      (value "SMT Mini Button")
      (footprint "eagle-import:TL3301SPF160QJ")
      (fields (field (name "MPN") "TL3301SPF160QJ"))
      (libsource (lib "eagle-import") (part "TAC_SWITCH_SMT"))
    )
    (comp (ref "S2")
      (value "SMT Mini Button")
      (footprint "eagle-import:TL3301SPF160QJ")
      (fields (field (name "MPN") "TL3301SPF160QJ"))
      (libsource (lib "eagle-import") (part "TAC_SWITCH_SMT"))
    )
    (comp (ref "U3")
      (value "MCP6004")
      (footprint "eagle-import:TSSOP-14")
      (fields (field (name "MPN") "MCP6004T-E/ST"))
      (libsource (lib "eagle-import") (part "MCP6004_TSSOP-14"))
    )
    (comp (ref "U6")
      (value "MCP6004")
      (footprint "eagle-import:TSSOP-14")
      (fields (field (name "MPN") "MCP6004T-E/ST"))
      (libsource (lib "eagle-import") (part "MCP6004_TSSOP-14"))
    )
    (comp (ref "U11")
      (value "CD4051 SO-16")
      (footprint "eagle-import:SO-16")
      (libsource (lib "eagle-import") (part "4051D"))
    )
    (comp (ref "VR_1")
      (value "M-10K-B-D")
      (footprint "eagle-import:9MM_SNAP-IN_POT_SILK")
      (libsource (lib "eagle-import") (part "POT_9MM_SNAP-IN__"))
    )
    (comp (ref "VR_2")
      (value "M-10K-B-D")
      (footprint "eagle-import:9MM_SNAP-IN_POT_SILK")
      (libsource (lib "eagle-import") (part "POT_9MM_SNAP-IN__"))
    )
    (comp (ref "VR_3")
      (value "M-10K-B-D")
      (footprint "eagle-import:9MM_SNAP-IN_POT_SILK")
      (libsource (lib "eagle-import") (part "POT_9MM_SNAP-IN__"))
    )
    (comp (ref "VR_4")
      (value "M-10K-B-D")
      (footprint "eagle-import:9MM_SNAP-IN_POT_SILK")
      (libsource (lib "eagle-import") (part "POT_9MM_SNAP-IN__"))
    )
    (comp (ref "VR_5")
      (value "M-10K-B-D")
      (footprint "eagle-import:9MM_SNAP-IN_POT_SILK")
      (libsource (lib "eagle-import") (part "POT_9MM_SNAP-IN__"))
    )
    (comp (ref "VR_6")
      (value "M-10K-B-D")
      (footprint "eagle-import:9MM_SNAP-IN_POT_SILK")
      (libsource (lib "eagle-import") (part "POT_9MM_SNAP-IN__"))
    )
    (comp (ref "VR_7")
      (value "M-10K-B-D")
      (footprint "eagle-import:9MM_SNAP-IN_POT_SILK")
      (libsource (lib "eagle-import") (part "POT_9MM_SNAP-IN__"))
    )
    (comp (ref "VR_8")
      (value "M-10K-B-D")
      (footprint "eagle-import:9MM_SNAP-IN_POT_SILK")
      (libsource (lib "eagle-import") (part "POT_9MM_CHASSIS_"))
    )
  )
  (nets
    (net (code "1") (name "+3V3_A") (class "Default")
      (node (ref "C4") (pin "2") (pinfunction "2_2") (pintype "passive"))
      (node (ref "C7") (pin "2") (pinfunction "2_2") (pintype "passive"))
      (node (ref "U1") (pin "21") (pinfunction "+3V3_A_21") (pintype "bidirectional"))
      (node (ref "U1") (pin "B21") (pinfunction "+3V3_A_B21") (pintype "bidirectional"))
      (node (ref "U11") (pin "16") (pinfunction "VCC_16") (pintype "power_in"))
      (node (ref "U6") (pin "4") (pinfunction "V+_4") (pintype "power_in"))
      (node (ref "VR_1") (pin "3") (pinfunction "3_3") (pintype "passive"))
      (node (ref "VR_2") (pin "3") (pinfunction "3_3") (pintype "passive"))
      (node (ref "VR_3") (pin "3") (pinfunction "3_3") (pintype "passive"))
      (node (ref "VR_4") (pin "3") (pinfunction "3_3") (pintype "passive"))
      (node (ref "VR_5") (pin "3") (pinfunction "3_3") (pintype "passive"))
      (node (ref "VR_6") (pin "3") (pinfunction "3_3") (pintype "passive"))
      (node (ref "VR_7") (pin "3") (pinfunction "3_3") (pintype "passive"))
      (node (ref "VR_8") (pin "3") (pinfunction "E_3") (pintype "passive"))
    )
    (net (code "2") (name "+3V3_D") (class "Default")
      (node (ref "C11") (pin "1") (pinfunction "1_1") (pintype "passive"))
      (node (ref "C6") (pin "2") (pinfunction "2_2") (pintype "passive"))
      (node (ref "LED_KNOBG1") (pin "ANODE") (pinfunction "A_ANODE") (pintype "passive"))
      (node (ref "LED_KNOBG2") (pin "ANODE") (pinfunction "A_ANODE") (pintype "passive"))
      (node (ref "LED_KNOBG3") (pin "ANODE") (pinfunction "A_ANODE") (pintype "passive"))
      (node (ref "LED_KNOBG4") (pin "ANODE") (pinfunction "A_ANODE") (pintype "passive"))
      (node (ref "LED_KNOBG5") (pin "ANODE") (pinfunction "A_ANODE") (pintype "passive"))
      (node (ref "LED_KNOBG6") (pin "ANODE") (pinfunction "A_ANODE") (pintype "passive"))
      (node (ref "LED_KNOBG7") (pin "ANODE") (pinfunction "A_ANODE") (pintype "passive"))
      (node (ref "LED_KNOBG8") (pin "ANODE") (pinfunction "A_ANODE") (pintype "passive"))
      (node (ref "R1") (pin "2") (pinfunction "2_2") (pintype "passive"))
      (node (ref "R16") (pin "2") (pinfunction "2_2") (pintype "passive"))
      (node (ref "R2") (pin "2") (pinfunction "2_2") (pintype "passive"))
      (node (ref "R29") (pin "2") (pinfunction "2_2") (pintype "passive"))
      (node (ref "R3") (pin "2") (pinfunction "2_2") (pintype "passive"))
      (node (ref "R4") (pin "2") (pinfunction "2_2") (pintype "passive"))
      (node (ref "R54") (pin "1") (pinfunction "1_1") (pintype "passive"))
      (node (ref "R64") (pin "1") (pinfunction "1_1") (pintype "passive"))
      (node (ref "R72") (pin "1") (pinfunction "1_1") (pintype "passive"))
      (node (ref "R73") (pin "1") (pinfunction "1_1") (pintype "passive"))
      (node (ref "U1") (pin "38") (pinfunction "+3V3_D_38") (pintype "bidirectional"))
      (node (ref "U1") (pin "B38") (pinfunction "+3V3_D_B38") (pintype "bidirectional"))
      (node (ref "U15") (pin "6") (pinfunction "V_6") (pintype "bidirectional"))
      (node (ref "U16") (pin "7A") (pinfunction "+3V3_7A") (pintype "bidirectional"))
      (node (ref "U2") (pin "P$4") (pinfunction "VCC_P$4") (pintype "bidirectional"))
      (node (ref "U5") (pin "2") (pinfunction "A1_2") (pintype "bidirectional"))
      (node (ref "U5") (pin "28") (pinfunction "VDD_28") (pintype "power_in"))
    )
    (net (code "3") (name "+3V3_OLED") (class "Default")
      (node (ref "C1") (pin "2") (pinfunction "2_2") (pintype "passive"))
      (node (ref "C16") (pin "1") (pinfunction "1_1") (pintype "passive"))
      (node (ref "L4") (pin "P$2") (pinfunction "P$2_P$2") (pintype "bidirectional"))
      (node (ref "R26") (pin "2") (pinfunction "2_2") (pintype "passive"))
      (node (ref "R87") (pin "2") (pinfunction "2_2") (pintype "passive"))
      (node (ref "U7") (pin "6") (pinfunction "VOS_6") (pintype "bidirectional"))
      (node (ref "U8") (pin "2") (pinfunction "VCC_2") (pintype "bidirectional"))
    )
    (net (code "4") (name "+5V") (class "Default")
      (node (ref "C5") (pin "1") (pinfunction "1_1") (pintype "passive"))
      (node (ref "L1") (pin "P$1") (pinfunction "P$1_P$1") (pintype "bidirectional"))
      (node (ref "R34") (pin "2") (pinfunction "2_2") (pintype "passive"))
      (node (ref "R42") (pin "2") (pinfunction "2_2") (pintype "passive"))
      (node (ref "R56") (pin "2") (pinfunction "2_2") (pintype "passive"))
      (node (ref "R60") (pin "2") (pinfunction "2_2") (pintype "passive"))
      (node (ref "U9") (pin "2") (pinfunction "OUT_2") (pintype "passive"))
      (node (ref "U9") (pin "TAB") (pinfunction "OUT1_TAB") (pintype "passive"))
    )
    (net (code "5") (name "+5V_ISOL") (class "Default")
      (node (ref "C14") (pin "2") (pinfunction "2_2") (pintype "passive"))
      (node (ref "C18") (pin "1") (pinfunction "1_1") (pintype "passive"))
      (node (ref "C23") (pin "1") (pinfunction "1_1") (pintype "passive"))
      (node (ref "C60") (pin "2") (pinfunction "2_2") (pintype "passive"))
      (node (ref "R32") (pin "2") (pinfunction "2_2") (pintype "passive"))
      (node (ref "R44") (pin "2") (pinfunction "2_2") (pintype "passive"))
      (node (ref "R67") (pin "2") (pinfunction "2_2") (pintype "passive"))
      (node (ref "U$4") (pin "P$5") (pinfunction "OUT+_P$5") (pintype "bidirectional"))
      (node (ref "U10") (pin "4") (pinfunction "V+_4") (pintype "power_in"))
      (node (ref "U3") (pin "4") (pinfunction "V+_4") (pintype "power_in"))
      (node (ref "U4") (pin "6") (pinfunction "VCC_6") (pintype "bidirectional"))
    )
    (net (code "6") (name "+9V") (class "Default")
      (node (ref "C13") (pin "1") (pinfunction "1_1") (pintype "passive"))
      (node (ref "C2") (pin "1") (pinfunction "1_1") (pintype "passive"))
      (node (ref "C3") (pin "1") (pinfunction "1_1") (pintype "passive"))
      (node (ref "D1") (pin "C") (pinfunction "C_C") (pintype "passive"))
      (node (ref "FB4") (pin "1") (pinfunction "1_1") (pintype "passive"))
      (node (ref "U1") (pin "39") (pinfunction "V_IN_39") (pintype "bidirectional"))
      (node (ref "U1") (pin "B39") (pinfunction "V_IN_B39") (pintype "bidirectional"))
      (node (ref "U9") (pin "3") (pinfunction "IN_3") (pintype "input"))
    )
    (net (code "7") (name "ADC_CV_1") (class "Default")
      (node (ref "C9") (pin "2") (pinfunction "2_2") (pintype "passive"))
      (node (ref "R68") (pin "2") (pinfunction "2_2") (pintype "passive"))
      (node (ref "U1") (pin "24") (pinfunction "GPIO17(ADC2)_24") (pintype "bidirectional"))
      (node (ref "U1") (pin "B24") (pinfunction "GPIO17(ADC2)_B24") (pintype "bidirectional"))
      (node (ref "U6") (pin "14") (pinfunction "OUT_14") (pintype "output"))
    )
    (net (code "8") (name "ADC_CV_2") (class "Default")
      (node (ref "C8") (pin "2") (pinfunction "2_2") (pintype "passive"))
      (node (ref "R36") (pin "2") (pinfunction "2_2") (pintype "passive"))
      (node (ref "U1") (pin "25") (pinfunction "GPIO18(ADC3)_25") (pintype "bidirectional"))
      (node (ref "U1") (pin "B25") (pinfunction "GPIO18(ADC3)_B25") (pintype "bidirectional"))
      (node (ref "U6") (pin "1") (pinfunction "OUT_1") (pintype "output"))
    )
    (net (code "9") (name "ADC_CV_3") (class "Default")
      (node (ref "C10") (pin "2") (pinfunction "2_2") (pintype "passive"))
      (node (ref "R50") (pin "2") (pinfunction "2_2") (pintype "passive"))
      (node (ref "U1") (pin "32") (pinfunction "GPIO25(ADC10)_32") (pintype "bidirectional"))
      (node (ref "U1") (pin "B32") (pinfunction "GPIO25(ADC10)_B32") (pintype "bidirectional"))
      (node (ref "U6") (pin "7") (pinfunction "OUT_7") (pintype "output"))
    )
    (net (code "10") (name "ADC_CV_4") (class "Default")
      (node (ref "C12") (pin "2") (pinfunction "2_2") (pintype "passive"))
      (node (ref "R58") (pin "2") (pinfunction "2_2") (pintype "passive"))
      (node (ref "U1") (pin "31") (pinfunction "GPIO24(ADC9)_31") (pintype "bidirectional"))
      (node (ref "U1") (pin "B31") (pinfunction "GPIO24(ADC9)_B31") (pintype "bidirectional"))
      (node (ref "U6") (pin "8") (pinfunction "OUT_8") (pintype "output"))
    )
    (net (code "11") (name "AUDIO_IN_1") (class "Default")
      (node (ref "U1") (pin "16") (pinfunction "AUDIO_IN_L_16") (pintype "bidirectional"))
      (node (ref "U1") (pin "B16") (pinfunction "AUDIO_IN_L_B16") (pintype "bidirectional"))
      (node (ref "U10") (pin "13") (pinfunction "-IN_13") (pintype "input"))
      (node (ref "U10") (pin "14") (pinfunction "OUT_14") (pintype "output"))
    )
    (net (code "12") (name "AUDIO_IN_1_EXT") (class "Default")
      (node (ref "C25") (pin "1") (pinfunction "1_1") (pintype "passive"))
      (node (ref "P1") (pin "11") (pinfunction "11_11") (pintype "passive"))
      (node (ref "P1") (pin "12") (pinfunction "12_12") (pintype "passive"))
      (node (ref "R65") (pin "2") (pinfunction "2_2") (pintype "passive"))
    )
    (net (code "13") (name "AUDIO_IN_1_JACKS") (class "Default")
      (node (ref "J8") (pin "2") (pinfunction "TIP_2") (pintype "passive"))
      (node (ref "J9") (pin "5") (pinfunction "TIP_SW_5") (pintype "passive"))
      (node (ref "P2") (pin "11") (pinfunction "11_11") (pintype "passive"))
      (node (ref "P2") (pin "12") (pinfunction "12_12") (pintype "passive"))
    )
    (net (code "14") (name "AUDIO_IN_2") (class "Default")
      (node (ref "U1") (pin "17") (pinfunction "AUDIO_IN_R_17") (pintype "bidirectional"))
      (node (ref "U1") (pin "B17") (pinfunction "AUDIO_IN_R_B17") (pintype "bidirectional"))
      (node (ref "U10") (pin "8") (pinfunction "OUT_8") (pintype "output"))
      (node (ref "U10") (pin "9") (pinfunction "-IN_9") (pintype "input"))
    )
    (net (code "15") (name "AUDIO_IN_2_EXT") (class "Default")
      (node (ref "C24") (pin "1") (pinfunction "1_1") (pintype "passive"))
      (node (ref "P1") (pin "10") (pinfunction "10_10") (pintype "passive"))
      (node (ref "P1") (pin "9") (pinfunction "9_9") (pintype "passive"))
      (node (ref "R53") (pin "2") (pinfunction "2_2") (pintype "passive"))
    )
    (net (code "16") (name "AUDIO_IN_2_JACKS") (class "Default")
      (node (ref "J9") (pin "2") (pinfunction "TIP_2") (pintype "passive"))
      (node (ref "P2") (pin "10") (pinfunction "10_10") (pintype "passive"))
      (node (ref "P2") (pin "9") (pinfunction "9_9") (pintype "passive"))
    )
    (net (code "17") (name "AUDIO_OUT_1") (class "Default")
      (node (ref "C19") (pin "1") (pinfunction "1_1") (pintype "passive"))
      (node (ref "U1") (pin "18") (pinfunction "AUDIO_OUT_L_18") (pintype "bidirectional"))
      (node (ref "U1") (pin "B18") (pinfunction "AUDIO_OUT_L_B18") (pintype "bidirectional"))
    )
    (net (code "18") (name "AUDIO_OUT_1_EXT") (class "Default")
      (node (ref "C20") (pin "2") (pinfunction "2_2") (pintype "passive"))
      (node (ref "R40") (pin "2") (pinfunction "2_2") (pintype "passive"))
      (node (ref "R5") (pin "2") (pinfunction "2_2") (pintype "passive"))
      (node (ref "VR1") (pin "3P") (pinfunction "3_3P") (pintype "passive"))
    )
    (net (code "19") (name "AUDIO_OUT_1_JACKS") (class "Default")
      (node (ref "J12") (pin "2") (pinfunction "TIP_2") (pintype "passive"))
      (node (ref "P2") (pin "7") (pinfunction "7_7") (pintype "passive"))
      (node (ref "P2") (pin "8") (pinfunction "8_8") (pintype "passive"))
    )
    (net (code "20") (name "AUDIO_OUT_2") (class "Default")
      (node (ref "C21") (pin "1") (pinfunction "1_1") (pintype "passive"))
      (node (ref "U1") (pin "19") (pinfunction "AUDIO_OUT_R_19") (pintype "bidirectional"))
      (node (ref "U1") (pin "B19") (pinfunction "AUDIO_OUT_R_B19") (pintype "bidirectional"))
    )
    (net (code "21") (name "AUDIO_OUT_2_EXT") (class "Default")
      (node (ref "C22") (pin "2") (pinfunction "2_2") (pintype "passive"))
      (node (ref "R13") (pin "2") (pinfunction "2_2") (pintype "passive"))
      (node (ref "R47") (pin "2") (pinfunction "2_2") (pintype "passive"))
      (node (ref "VR1") (pin "3") (pinfunction "3_3") (pintype "passive"))
    )
    (net (code "22") (name "AUDIO_OUT_2_JACKS") (class "Default")
      (node (ref "J13") (pin "2") (pinfunction "TIP_2") (pintype "passive"))
      (node (ref "P2") (pin "5") (pinfunction "5_5") (pintype "passive"))
      (node (ref "P2") (pin "6") (pinfunction "6_6") (pintype "passive"))
    )
    (net (code "23") (name "CD4021_CLK") (class "Default")
      (node (ref "U1") (pin "35") (pinfunction "GPIO28(ADC11)_35") (pintype "bidirectional"))
      (node (ref "U1") (pin "B35") (pinfunction "GPIO28(ADC11)_B35") (pintype "bidirectional"))
      (node (ref "U16") (pin "2A") (pinfunction "CD4021_CLK_2A") (pintype "bidirectional"))
    )
    (net (code "24") (name "CD4021_CS") (class "Default")
      (node (ref "U1") (pin "34") (pinfunction "GPIO27(SAI2_FS_B)_34") (pintype "bidirectional"))
      (node (ref "U1") (pin "B34") (pinfunction "GPIO27(SAI2_FS_B)_B34") (pintype "bidirectional"))
      (node (ref "U16") (pin "3A") (pinfunction "CD4021_CS_3A") (pintype "bidirectional"))
    )
    (net (code "25") (name "CD4021_D1") (class "Default")
      (node (ref "U1") (pin "33") (pinfunction "GPIO26(SAI2_SD_A)_33") (pintype "bidirectional"))
      (node (ref "U1") (pin "B33") (pinfunction "GPIO26(SAI2_SD_A)_B33") (pintype "bidirectional"))
      (node (ref "U16") (pin "1A") (pinfunction "CD4021_D1_1A") (pintype "bidirectional"))
    )
    (net (code "26") (name "CV_OUT_1") (class "Default")
      (node (ref "J_CV_OUT_1") (pin "TIP") (pinfunction "TIP_TIP") (pintype "passive"))
      (node (ref "R14") (pin "2") (pinfunction "2_2") (pintype "passive"))
    )
    (net (code "27") (name "CV_OUT_2") (class "Default")
      (node (ref "J_CV_OUT_2") (pin "TIP") (pinfunction "TIP_TIP") (pintype "passive"))
      (node (ref "R15") (pin "2") (pinfunction "2_2") (pintype "passive"))
    )
    (net (code "28") (name "DAC_OUT_1") (class "Default")
      (node (ref "U1") (pin "30") (pinfunction "GPIO23(ADC8/DAC1)_30") (pintype "bidirectional"))
      (node (ref "U1") (pin "B30") (pinfunction "GPIO23(ADC8/DAC1)_B30") (pintype "bidirectional"))
      (node (ref "U3") (pin "12") (pinfunction "+IN_12") (pintype "input"))
    )
    (net (code "29") (name "DAC_OUT_2") (class "Default")
      (node (ref "U1") (pin "29") (pinfunction "GPIO22(ADC7/DAC2)_29") (pintype "bidirectional"))
      (node (ref "U1") (pin "B29") (pinfunction "GPIO22(ADC7/DAC2)_B29") (pintype "bidirectional"))
      (node (ref "U3") (pin "5") (pinfunction "+IN_5") (pintype "input"))
    )
    (net (code "30") (name "GATE_IN") (class "Default")
      (node (ref "R30") (pin "1") (pinfunction "1_1") (pintype "passive"))
      (node (ref "U1") (pin "1") (pinfunction "GPIO0(USB_HS_ID)_1") (pintype "bidirectional"))
      (node (ref "U1") (pin "B1") (pinfunction "GPIO0(USB_HS_ID)_B1") (pintype "bidirectional"))
    )
    (net (code "31") (name "GATE_JACK_IN") (class "Default")
      (node (ref "J_GATE_IN_1") (pin "TIP") (pinfunction "TIP_TIP") (pintype "passive"))
      (node (ref "R22") (pin "1") (pinfunction "1_1") (pintype "passive"))
    )
    (net (code "32") (name "GATE_OUT") (class "Default")
      (node (ref "U1") (pin "22") (pinfunction "GPIO15(ADC0)_22") (pintype "bidirectional"))
      (node (ref "U1") (pin "B22") (pinfunction "GPIO15(ADC0)_B22") (pintype "bidirectional"))
      (node (ref "U3") (pin "10") (pinfunction "+IN_10") (pintype "input"))
    )
    (net (code "33") (name "GND") (class "Default")
      (node (ref "C1") (pin "1") (pinfunction "1_1") (pintype "passive"))
      (node (ref "C11") (pin "2") (pinfunction "2_2") (pintype "passive"))
      (node (ref "C13") (pin "2") (pinfunction "2_2") (pintype "passive"))
      (node (ref "C14") (pin "1") (pinfunction "1_1") (pintype "passive"))
      (node (ref "C15") (pin "1") (pinfunction "1_1") (pintype "passive"))
      (node (ref "C16") (pin "2") (pinfunction "2_2") (pintype "passive"))
      (node (ref "C17") (pin "2") (pinfunction "2_2") (pintype "passive"))
      (node (ref "C18") (pin "2") (pinfunction "2_2") (pintype "passive"))
      (node (ref "C2") (pin "2") (pinfunction "2_2") (pintype "passive"))
      (node (ref "C23") (pin "2") (pinfunction "2_2") (pintype "passive"))
      (node (ref "C3") (pin "2") (pinfunction "2_2") (pintype "passive"))
      (node (ref "C4") (pin "1") (pinfunction "1_1") (pintype "passive"))
      (node (ref "C5") (pin "2") (pinfunction "2_2") (pintype "passive"))
      (node (ref "C56") (pin "1") (pinfunction "1_1") (pintype "passive"))
      (node (ref "C59") (pin "2") (pinfunction "2_2") (pintype "passive"))
      (node (ref "C6") (pin "1") (pinfunction "1_1") (pintype "passive"))
      (node (ref "C60") (pin "1") (pinfunction "1_1") (pintype "passive"))
      (node (ref "C7") (pin "1") (pinfunction "1_1") (pintype "passive"))
      (node (ref "H3") (pin "B3,2") (pinfunction "MOUNT_B3,2") (pintype "passive"))
      (node (ref "J7") (pin "1") (pinfunction "GND_1") (pintype "passive"))
      (node (ref "J7") (pin "4") (pinfunction "GND_4") (pintype "passive"))
      (node (ref "J_CV_1") (pin "GND") (pinfunction "GND_GND") (pintype "passive"))
      (node (ref "J_CV_1") (pin "NORM") (pinfunction "NORM_NORM") (pintype "passive"))
      (node (ref "J_CV_2") (pin "GND") (pinfunction "GND_GND") (pintype "passive"))
      (node (ref "J_CV_2") (pin "NORM") (pinfunction "NORM_NORM") (pintype "passive"))
      (node (ref "J_CV_3") (pin "GND") (pinfunction "GND_GND") (pintype "passive"))
      (node (ref "J_CV_3") (pin "NORM") (pinfunction "NORM_NORM") (pintype "passive"))
      (node (ref "J_CV_4") (pin "GND") (pinfunction "GND_GND") (pintype "passive"))
      (node (ref "J_CV_4") (pin "NORM") (pinfunction "NORM_NORM") (pintype "passive"))
      (node (ref "J_CV_OUT_1") (pin "GND") (pinfunction "GND_GND") (pintype "passive"))
      (node (ref "J_CV_OUT_2") (pin "GND") (pinfunction "GND_GND") (pintype "passive"))
      (node (ref "J_GATE_IN_1") (pin "GND") (pinfunction "GND_GND") (pintype "passive"))
      (node (ref "J_GATE_OUT") (pin "GND") (pinfunction "GND_GND") (pintype "passive"))
      (node (ref "J_MIDI_IN") (pin "GND") (pinfunction "GND_GND") (pintype "passive"))
      (node (ref "J_MIDI_OUT") (pin "GND") (pinfunction "GND_GND") (pintype "passive"))
      (node (ref "P1") (pin "13") (pinfunction "13_13") (pintype "passive"))
      (node (ref "P1") (pin "14") (pinfunction "14_14") (pintype "passive"))
      (node (ref "P1") (pin "15") (pinfunction "15_15") (pintype "passive"))
      (node (ref "P1") (pin "16") (pinfunction "16_16") (pintype "passive"))
      (node (ref "P1") (pin "3") (pinfunction "3_3") (pintype "passive"))
      (node (ref "P1") (pin "4") (pinfunction "4_4") (pintype "passive"))
      (node (ref "Q1") (pin "E") (pinfunction "E_E") (pintype "passive"))
      (node (ref "R11") (pin "1") (pinfunction "1_1") (pintype "passive"))
      (node (ref "R18") (pin "1") (pinfunction "1_1") (pintype "passive"))
      (node (ref "R28") (pin "1") (pinfunction "1_1") (pintype "passive"))
      (node (ref "R35") (pin "2") (pinfunction "2_2") (pintype "passive"))
      (node (ref "R38") (pin "1") (pinfunction "1_1") (pintype "passive"))
      (node (ref "R40") (pin "1") (pinfunction "1_1") (pintype "passive"))
      (node (ref "R46") (pin "1") (pinfunction "1_1") (pintype "passive"))
      (node (ref "R47") (pin "1") (pinfunction "1_1") (pintype "passive"))
      (node (ref "R49") (pin "2") (pinfunction "2_2") (pintype "passive"))
      (node (ref "R53") (pin "1") (pinfunction "1_1") (pintype "passive"))
      (node (ref "R57") (pin "2") (pinfunction "2_2") (pintype "passive"))
      (node (ref "R61") (pin "2") (pinfunction "2_2") (pintype "passive"))
      (node (ref "R65") (pin "1") (pinfunction "1_1") (pintype "passive"))
      (node (ref "R66") (pin "1") (pinfunction "1_1") (pintype "passive"))
      (node (ref "R88") (pin "1") (pinfunction "1_1") (pintype "passive"))
      (node (ref "R9") (pin "1") (pinfunction "1_1") (pintype "passive"))
      (node (ref "S1") (pin "3") (pinfunction "3_3") (pintype "passive"))
      (node (ref "S1") (pin "4") (pinfunction "4_4") (pintype "passive"))
      (node (ref "S2") (pin "3") (pinfunction "3_3") (pintype "passive"))
      (node (ref "S2") (pin "4") (pinfunction "4_4") (pintype "passive"))
      (node (ref "U$4") (pin "P$1") (pinfunction "IN-_P$1") (pintype "bidirectional"))
      (node (ref "U$4") (pin "P$4") (pinfunction "OUT-_P$4") (pintype "bidirectional"))
      (node (ref "U1") (pin "20") (pinfunction "AGND_20") (pintype "bidirectional"))
      (node (ref "U1") (pin "40") (pinfunction "GND_40") (pintype "bidirectional"))
      (node (ref "U1") (pin "B20") (pinfunction "AGND_B20") (pintype "bidirectional"))
      (node (ref "U1") (pin "B40") (pinfunction "GND_B40") (pintype "bidirectional"))
      (node (ref "U10") (pin "11") (pinfunction "V-_11") (pintype "power_in"))
      (node (ref "U11") (pin "6") (pinfunction "INH_6") (pintype "input"))
      (node (ref "U11") (pin "7") (pinfunction "VEE_7") (pintype "power_in"))
      (node (ref "U11") (pin "8") (pinfunction "GND_8") (pintype "power_in"))
      (node (ref "U15") (pin "5") (pinfunction "GND_5") (pintype "bidirectional"))
      (node (ref "U16") (pin "6A") (pinfunction "GND_6A") (pintype "bidirectional"))
      (node (ref "U2") (pin "GND1") (pinfunction "SHIELD_GND1") (pintype "bidirectional"))
      (node (ref "U2") (pin "GND2") (pinfunction "SHIELD_GND2") (pintype "bidirectional"))
      (node (ref "U2") (pin "P$6") (pinfunction "GND_P$6") (pintype "bidirectional"))
      (node (ref "U3") (pin "11") (pinfunction "V-_11") (pintype "power_in"))
      (node (ref "U4") (pin "2") (pinfunction "GND_2") (pintype "bidirectional"))
      (node (ref "U4") (pin "3") (pinfunction "SDOWN_3") (pintype "bidirectional"))
      (node (ref "U4") (pin "9") (pinfunction "GND_9") (pintype "bidirectional"))
      (node (ref "U5") (pin "1") (pinfunction "A0_1") (pintype "bidirectional"))
      (node (ref "U5") (pin "14") (pinfunction "GND_14") (pintype "power_in"))
      (node (ref "U5") (pin "23") (pinfunction "/OE_23") (pintype "bidirectional"))
      (node (ref "U5") (pin "24") (pinfunction "A5_24") (pintype "bidirectional"))
      (node (ref "U5") (pin "25") (pinfunction "EXTCLK_25") (pintype "input"))
      (node (ref "U5") (pin "3") (pinfunction "A2_3") (pintype "bidirectional"))
      (node (ref "U5") (pin "4") (pinfunction "A3_4") (pintype "bidirectional"))
      (node (ref "U5") (pin "5") (pinfunction "A4_5") (pintype "bidirectional"))
      (node (ref "U6") (pin "11") (pinfunction "V-_11") (pintype "power_in"))
      (node (ref "U7") (pin "1") (pinfunction "PGND_1") (pintype "bidirectional"))
      (node (ref "U7") (pin "4") (pinfunction "AGND_4") (pintype "bidirectional"))
      (node (ref "U7") (pin "P$1") (pinfunction "PAD_P$1") (pintype "bidirectional"))
      (node (ref "U7") (pin "P$9") (pinfunction "PAD_P$9") (pintype "bidirectional"))
      (node (ref "U8") (pin "1") (pinfunction "GND_1") (pintype "bidirectional"))
      (node (ref "U9") (pin "1") (pinfunction "GND_1") (pintype "input"))
      (node (ref "VR1") (pin "1") (pinfunction "1_1") (pintype "passive"))
      (node (ref "VR1") (pin "1P") (pinfunction "1_1P") (pintype "passive"))
      (node (ref "VR_1") (pin "1") (pinfunction "1_1") (pintype "passive"))
      (node (ref "VR_2") (pin "1") (pinfunction "1_1") (pintype "passive"))
      (node (ref "VR_3") (pin "1") (pinfunction "1_1") (pintype "passive"))
      (node (ref "VR_4") (pin "1") (pinfunction "1_1") (pintype "passive"))
      (node (ref "VR_5") (pin "1") (pinfunction "1_1") (pintype "passive"))
      (node (ref "VR_6") (pin "1") (pinfunction "1_1") (pintype "passive"))
      (node (ref "VR_7") (pin "1") (pinfunction "1_1") (pintype "passive"))
      (node (ref "VR_8") (pin "1") (pinfunction "A_1") (pintype "passive"))
      (node (ref "VR_8") (pin "CHASSIS1") (pinfunction "CHASSIS_CHASSIS1") (pintype "passive"))
      (node (ref "VR_8") (pin "CHASSIS2") (pinfunction "CHASSIS_CHASSIS2") (pintype "passive"))
    )
    (net (code "34") (name "GND_2") (class "Default")
      (node (ref "J10") (pin "1") (pinfunction "SLEEVE_1") (pintype "passive"))
      (node (ref "J10") (pin "4") (pinfunction "SLEEVE_SW_4") (pintype "passive"))
      (node (ref "J12") (pin "1") (pinfunction "SLEEVE_1") (pintype "passive"))
      (node (ref "J12") (pin "4") (pinfunction "SLEEVE_SW_4") (pintype "passive"))
      (node (ref "J13") (pin "1") (pinfunction "SLEEVE_1") (pintype "passive"))
      (node (ref "J13") (pin "4") (pinfunction "SLEEVE_SW_4") (pintype "passive"))
      (node (ref "J8") (pin "1") (pinfunction "SLEEVE_1") (pintype "passive"))
      (node (ref "J8") (pin "4") (pinfunction "SLEEVE_SW_4") (pintype "passive"))
      (node (ref "J9") (pin "1") (pinfunction "SLEEVE_1") (pintype "passive"))
      (node (ref "J9") (pin "4") (pinfunction "SLEEVE_SW_4") (pintype "passive"))
      (node (ref "P2") (pin "13") (pinfunction "13_13") (pintype "passive"))
      (node (ref "P2") (pin "14") (pinfunction "14_14") (pintype "passive"))
      (node (ref "P2") (pin "15") (pinfunction "15_15") (pintype "passive"))
      (node (ref "P2") (pin "16") (pinfunction "16_16") (pintype "passive"))
      (node (ref "P2") (pin "3") (pinfunction "3_3") (pintype "passive"))
      (node (ref "P2") (pin "4") (pinfunction "4_4") (pintype "passive"))
    )
    (net (code "35") (name "HEADPHONE_OUT_L") (class "Default")
      (node (ref "C62") (pin "-") (pinfunction "NEG_-") (pintype "passive"))
      (node (ref "P1") (pin "2") (pinfunction "2_2") (pintype "passive"))
    )
    (net (code "36") (name "HEADPHONE_OUT_R") (class "Default")
      (node (ref "C63") (pin "-") (pinfunction "NEG_-") (pintype "passive"))
      (node (ref "P1") (pin "1") (pinfunction "1_1") (pintype "passive"))
    )
    (net (code "37") (name "HEADPHONE_WIPER_L") (class "Default")
      (node (ref "C53") (pin "1") (pinfunction "1_1") (pintype "passive"))
      (node (ref "R7") (pin "2") (pinfunction "2_2") (pintype "passive"))
      (node (ref "VR1") (pin "2P") (pinfunction "2_2P") (pintype "passive"))
    )
    (net (code "38") (name "HEADPHONE_WIPER_R") (class "Default")
      (node (ref "C54") (pin "1") (pinfunction "1_1") (pintype "passive"))
      (node (ref "R20") (pin "2") (pinfunction "2_2") (pintype "passive"))
      (node (ref "VR1") (pin "2") (pinfunction "2_2") (pintype "passive"))
    )
    (net (code "39") (name "HP_OUT_L_EXT") (class "Default")
      (node (ref "J10") (pin "2") (pinfunction "TIP_2") (pintype "passive"))
      (node (ref "P2") (pin "2") (pinfunction "2_2") (pintype "passive"))
    )
    (net (code "40") (name "HP_OUT_R_EXT") (class "Default")
      (node (ref "J10") (pin "3") (pinfunction "RING_3") (pintype "passive"))
      (node (ref "P2") (pin "1") (pinfunction "1_1") (pintype "passive"))
    )
    (net (code "41") (name "I2C1_SCL") (class "Default")
      (node (ref "R73") (pin "2") (pinfunction "2_2") (pintype "passive"))
      (node (ref "U1") (pin "12") (pinfunction "GPIO11(I2C1_SCL)_12") (pintype "bidirectional"))
      (node (ref "U1") (pin "B12") (pinfunction "GPIO11(I2C1_SCL)_B12") (pintype "bidirectional"))
      (node (ref "U16") (pin "5A") (pinfunction "I2C_SCL_5A") (pintype "bidirectional"))
      (node (ref "U5") (pin "26") (pinfunction "SCL_26") (pintype "bidirectional"))
    )
    (net (code "42") (name "I2C1_SDA") (class "Default")
      (node (ref "R72") (pin "2") (pinfunction "2_2") (pintype "passive"))
      (node (ref "U1") (pin "13") (pinfunction "GPIO12(I2C1_SDA)_13") (pintype "bidirectional"))
      (node (ref "U1") (pin "B13") (pinfunction "GPIO12(I2C1_SDA)_B13") (pintype "bidirectional"))
      (node (ref "U16") (pin "4A") (pinfunction "I2C_SDA_4A") (pintype "bidirectional"))
      (node (ref "U5") (pin "27") (pinfunction "SDA_27") (pintype "bidirectional"))
    )
    (net (code "43") (name "LED_KNOB_1_G") (class "Default")
      (node (ref "R6") (pin "1") (pinfunction "1_1") (pintype "passive"))
      (node (ref "U5") (pin "6") (pinfunction "LED0_6") (pintype "bidirectional"))
    )
    (net (code "44") (name "LED_KNOB_2_G") (class "Default")
      (node (ref "R12") (pin "1") (pinfunction "1_1") (pintype "passive"))
      (node (ref "U5") (pin "7") (pinfunction "LED1_7") (pintype "bidirectional"))
    )
    (net (code "45") (name "LED_KNOB_3_G") (class "Default")
      (node (ref "R19") (pin "1") (pinfunction "1_1") (pintype "passive"))
      (node (ref "U5") (pin "8") (pinfunction "LED2_8") (pintype "bidirectional"))
    )
    (net (code "46") (name "LED_KNOB_4_G") (class "Default")
      (node (ref "R25") (pin "1") (pinfunction "1_1") (pintype "passive"))
      (node (ref "U5") (pin "9") (pinfunction "LED3_9") (pintype "bidirectional"))
    )
    (net (code "47") (name "LED_KNOB_5_G") (class "Default")
      (node (ref "R31") (pin "1") (pinfunction "1_1") (pintype "passive"))
      (node (ref "U5") (pin "10") (pinfunction "LED4_10") (pintype "bidirectional"))
    )
    (net (code "48") (name "LED_KNOB_6_G") (class "Default")
      (node (ref "R37") (pin "1") (pinfunction "1_1") (pintype "passive"))
      (node (ref "U5") (pin "11") (pinfunction "LED5_11") (pintype "bidirectional"))
    )
    (net (code "49") (name "LED_KNOB_7_G") (class "Default")
      (node (ref "R43") (pin "1") (pinfunction "1_1") (pintype "passive"))
      (node (ref "U5") (pin "12") (pinfunction "LED6_12") (pintype "bidirectional"))
    )
    (net (code "50") (name "LED_KNOB_8_G") (class "Default")
      (node (ref "R52") (pin "1") (pinfunction "1_1") (pintype "passive"))
      (node (ref "U5") (pin "13") (pinfunction "LED7_13") (pintype "bidirectional"))
    )
    (net (code "51") (name "MIDI_IN_A") (class "Default")
      (node (ref "R63") (pin "2") (pinfunction "2_2") (pintype "passive"))
      (node (ref "R78") (pin "1") (pinfunction "1_1") (pintype "passive"))
      (node (ref "R79") (pin "1") (pinfunction "1_1") (pintype "passive"))
    )
    (net (code "52") (name "MIDI_IN_B") (class "Default")
      (node (ref "D5") (pin "A") (pinfunction "A_A") (pintype "passive"))
      (node (ref "R83") (pin "1") (pinfunction "1_1") (pintype "passive"))
      (node (ref "R84") (pin "1") (pinfunction "1_1") (pintype "passive"))
      (node (ref "U15") (pin "2") (pinfunction "C_2") (pintype "bidirectional"))
    )
    (net (code "53") (name "MIDI_IN_RING") (class "Default")
      (node (ref "J_MIDI_IN") (pin "RING") (pinfunction "NORM_RING") (pintype "passive"))
      (node (ref "R79") (pin "2") (pinfunction "2_2") (pintype "passive"))
      (node (ref "R84") (pin "2") (pinfunction "2_2") (pintype "passive"))
    )
    (net (code "54") (name "MIDI_IN_TIP") (class "Default")
      (node (ref "J_MIDI_IN") (pin "TIP") (pinfunction "TIP_TIP") (pintype "passive"))
      (node (ref "R78") (pin "2") (pinfunction "2_2") (pintype "passive"))
      (node (ref "R83") (pin "2") (pinfunction "2_2") (pintype "passive"))
    )
    (net (code "55") (name "MUX_SEL_0") (class "Default")
      (node (ref "U1") (pin "28") (pinfunction "GPIO21(ADC6)_28") (pintype "bidirectional"))
      (node (ref "U1") (pin "B28") (pinfunction "GPIO21(ADC6)_B28") (pintype "bidirectional"))
      (node (ref "U11") (pin "11") (pinfunction "A_11") (pintype "input"))
    )
    (net (code "56") (name "MUX_SEL_1") (class "Default")
      (node (ref "U1") (pin "27") (pinfunction "GPIO20(ADC5)_27") (pintype "bidirectional"))
      (node (ref "U1") (pin "B27") (pinfunction "GPIO20(ADC5)_B27") (pintype "bidirectional"))
      (node (ref "U11") (pin "10") (pinfunction "B_10") (pintype "input"))
    )
    (net (code "57") (name "MUX_SEL_2") (class "Default")
      (node (ref "U1") (pin "26") (pinfunction "GPIO19(ADC4)_26") (pintype "bidirectional"))
      (node (ref "U1") (pin "B26") (pinfunction "GPIO19(ADC4)_B26") (pintype "bidirectional"))
      (node (ref "U11") (pin "9") (pinfunction "C_9") (pintype "input"))
    )
    (net (code "58") (name "Net-(C20-Pad1)") (class "Default")
      (node (ref "C20") (pin "1") (pinfunction "1_1") (pintype "passive"))
      (node (ref "R69") (pin "1") (pinfunction "1_1") (pintype "passive"))
    )
    (net (code "59") (name "Net-(C22-Pad1)") (class "Default")
      (node (ref "C22") (pin "1") (pinfunction "1_1") (pintype "passive"))
      (node (ref "R71") (pin "1") (pinfunction "1_1") (pintype "passive"))
    )
    (net (code "60") (name "Net-(C53-Pad2)") (class "Default")
      (node (ref "C53") (pin "2") (pinfunction "2_2") (pintype "passive"))
      (node (ref "R23") (pin "2") (pinfunction "2_2") (pintype "passive"))
    )
    (net (code "61") (name "Net-(C54-Pad2)") (class "Default")
      (node (ref "C54") (pin "2") (pinfunction "2_2") (pintype "passive"))
      (node (ref "R24") (pin "2") (pinfunction "2_2") (pintype "passive"))
    )
    (net (code "62") (name "Net-(C62-POS)") (class "Default")
      (node (ref "C62") (pin "+") (pinfunction "POS_+") (pintype "passive"))
      (node (ref "R27") (pin "1") (pinfunction "1_1") (pintype "passive"))
      (node (ref "U4") (pin "7") (pinfunction "OUT1_7") (pintype "bidirectional"))
    )
    (net (code "63") (name "Net-(C63-POS)") (class "Default")
      (node (ref "C63") (pin "+") (pinfunction "POS_+") (pintype "passive"))
      (node (ref "R33") (pin "1") (pinfunction "1_1") (pintype "passive"))
      (node (ref "U4") (pin "5") (pinfunction "OUT2_5") (pintype "bidirectional"))
    )
    (net (code "64") (name "Net-(J7-PIN)") (class "Default")
      (node (ref "D1") (pin "A") (pinfunction "A_A") (pintype "passive"))
      (node (ref "J7") (pin "3") (pinfunction "PIN_3") (pintype "passive"))
    )
    (net (code "65") (name "Net-(J_CV_1-PadTIP)") (class "Default")
      (node (ref "J_CV_1") (pin "TIP") (pinfunction "TIP_TIP") (pintype "passive"))
      (node (ref "R70") (pin "1") (pinfunction "1_1") (pintype "passive"))
    )
    (net (code "66") (name "Net-(J_CV_2-PadTIP)") (class "Default")
      (node (ref "J_CV_2") (pin "TIP") (pinfunction "TIP_TIP") (pintype "passive"))
      (node (ref "R41") (pin "1") (pinfunction "1_1") (pintype "passive"))
    )
    (net (code "67") (name "Net-(J_CV_3-PadTIP)") (class "Default")
      (node (ref "J_CV_3") (pin "TIP") (pinfunction "TIP_TIP") (pintype "passive"))
      (node (ref "R51") (pin "1") (pinfunction "1_1") (pintype "passive"))
    )
    (net (code "68") (name "Net-(J_CV_4-PadTIP)") (class "Default")
      (node (ref "J_CV_4") (pin "TIP") (pinfunction "TIP_TIP") (pintype "passive"))
      (node (ref "R59") (pin "1") (pinfunction "1_1") (pintype "passive"))
    )
    (net (code "69") (name "Net-(J_GATE_OUT-PadTIP)") (class "Default")
      (node (ref "J_GATE_OUT") (pin "TIP") (pinfunction "TIP_TIP") (pintype "passive"))
      (node (ref "R21") (pin "2") (pinfunction "2_2") (pintype "passive"))
    )
    (net (code "70") (name "Net-(J_MIDI_OUT-NORM)") (class "Default")
      (node (ref "J_MIDI_OUT") (pin "RING") (pinfunction "NORM_RING") (pintype "passive"))
      (node (ref "R54") (pin "2") (pinfunction "2_2") (pintype "passive"))
    )
    (net (code "71") (name "Net-(J_MIDI_OUT-PadTIP)") (class "Default")
      (node (ref "J_MIDI_OUT") (pin "TIP") (pinfunction "TIP_TIP") (pintype "passive"))
      (node (ref "R55") (pin "1") (pinfunction "1_1") (pintype "passive"))
    )
    (net (code "72") (name "Net-(LED_KNOBG1-C)") (class "Default")
      (node (ref "LED_KNOBG1") (pin "CATHODE") (pinfunction "C_CATHODE") (pintype "passive"))
      (node (ref "R6") (pin "2") (pinfunction "2_2") (pintype "passive"))
    )
    (net (code "73") (name "Net-(LED_KNOBG2-C)") (class "Default")
      (node (ref "LED_KNOBG2") (pin "CATHODE") (pinfunction "C_CATHODE") (pintype "passive"))
      (node (ref "R12") (pin "2") (pinfunction "2_2") (pintype "passive"))
    )
    (net (code "74") (name "Net-(LED_KNOBG3-C)") (class "Default")
      (node (ref "LED_KNOBG3") (pin "CATHODE") (pinfunction "C_CATHODE") (pintype "passive"))
      (node (ref "R19") (pin "2") (pinfunction "2_2") (pintype "passive"))
    )
    (net (code "75") (name "Net-(LED_KNOBG4-C)") (class "Default")
      (node (ref "LED_KNOBG4") (pin "CATHODE") (pinfunction "C_CATHODE") (pintype "passive"))
      (node (ref "R25") (pin "2") (pinfunction "2_2") (pintype "passive"))
    )
    (net (code "76") (name "Net-(LED_KNOBG5-C)") (class "Default")
      (node (ref "LED_KNOBG5") (pin "CATHODE") (pinfunction "C_CATHODE") (pintype "passive"))
      (node (ref "R31") (pin "2") (pinfunction "2_2") (pintype "passive"))
    )
    (net (code "77") (name "Net-(LED_KNOBG6-C)") (class "Default")
      (node (ref "LED_KNOBG6") (pin "CATHODE") (pinfunction "C_CATHODE") (pintype "passive"))
      (node (ref "R37") (pin "2") (pinfunction "2_2") (pintype "passive"))
    )
    (net (code "78") (name "Net-(LED_KNOBG7-C)") (class "Default")
      (node (ref "LED_KNOBG7") (pin "CATHODE") (pinfunction "C_CATHODE") (pintype "passive"))
      (node (ref "R43") (pin "2") (pinfunction "2_2") (pintype "passive"))
    )
    (net (code "79") (name "Net-(LED_KNOBG8-C)") (class "Default")
      (node (ref "LED_KNOBG8") (pin "CATHODE") (pinfunction "C_CATHODE") (pintype "passive"))
      (node (ref "R52") (pin "2") (pinfunction "2_2") (pintype "passive"))
    )
    (net (code "80") (name "Net-(Q1-PadB)") (class "Default")
      (node (ref "Q1") (pin "B") (pinfunction "B_B") (pintype "passive"))
      (node (ref "R22") (pin "2") (pinfunction "2_2") (pintype "passive"))
      (node (ref "R28") (pin "2") (pinfunction "2_2") (pintype "passive"))
    )
    (net (code "81") (name "Net-(Q1-PadC)") (class "Default")
      (node (ref "Q1") (pin "C") (pinfunction "C_C") (pintype "passive"))
      (node (ref "R29") (pin "1") (pinfunction "1_1") (pintype "passive"))
      (node (ref "R30") (pin "2") (pinfunction "2_2") (pintype "passive"))
    )
    (net (code "82") (name "Net-(U$4-IN+)") (class "Default")
      (node (ref "C17") (pin "1") (pinfunction "1_1") (pintype "passive"))
      (node (ref "L1") (pin "P$2") (pinfunction "P$2_P$2") (pintype "bidirectional"))
      (node (ref "U$4") (pin "P$2") (pinfunction "IN+_P$2") (pintype "bidirectional"))
    )
    (net (code "83") (name "Net-(U3A-+IN)") (class "Default")
      (node (ref "R66") (pin "2") (pinfunction "2_2") (pintype "passive"))
      (node (ref "R67") (pin "1") (pinfunction "1_1") (pintype "passive"))
      (node (ref "U3") (pin "3") (pinfunction "+IN_3") (pintype "input"))
    )
    (net (code "84") (name "Net-(U3B--IN)") (class "Default")
      (node (ref "R10") (pin "1") (pinfunction "1_1") (pintype "passive"))
      (node (ref "R11") (pin "2") (pinfunction "2_2") (pintype "passive"))
      (node (ref "U3") (pin "6") (pinfunction "-IN_6") (pintype "input"))
    )
    (net (code "85") (name "Net-(U3B-OUT)") (class "Default")
      (node (ref "R10") (pin "2") (pinfunction "2_2") (pintype "passive"))
      (node (ref "R15") (pin "1") (pinfunction "1_1") (pintype "passive"))
      (node (ref "U3") (pin "7") (pinfunction "OUT_7") (pintype "output"))
    )
    (net (code "86") (name "Net-(U3C--IN)") (class "Default")
      (node (ref "R17") (pin "1") (pinfunction "1_1") (pintype "passive"))
      (node (ref "R18") (pin "2") (pinfunction "2_2") (pintype "passive"))
      (node (ref "U3") (pin "9") (pinfunction "-IN_9") (pintype "input"))
    )
    (net (code "87") (name "Net-(U3C-OUT)") (class "Default")
      (node (ref "R17") (pin "2") (pinfunction "2_2") (pintype "passive"))
      (node (ref "R21") (pin "1") (pinfunction "1_1") (pintype "passive"))
      (node (ref "U3") (pin "8") (pinfunction "OUT_8") (pintype "output"))
    )
    (net (code "88") (name "Net-(U3D--IN)") (class "Default")
      (node (ref "R8") (pin "1") (pinfunction "1_1") (pintype "passive"))
      (node (ref "R9") (pin "2") (pinfunction "2_2") (pintype "passive"))
      (node (ref "U3") (pin "13") (pinfunction "-IN_13") (pintype "input"))
    )
    (net (code "89") (name "Net-(U3D-OUT)") (class "Default")
      (node (ref "R14") (pin "1") (pinfunction "1_1") (pintype "passive"))
      (node (ref "R8") (pin "2") (pinfunction "2_2") (pintype "passive"))
      (node (ref "U3") (pin "14") (pinfunction "OUT_14") (pintype "output"))
    )
    (net (code "90") (name "Net-(U4-BPASS)") (class "Default")
      (node (ref "C56") (pin "2") (pinfunction "2_2") (pintype "passive"))
      (node (ref "U4") (pin "1") (pinfunction "BPASS_1") (pintype "bidirectional"))
    )
    (net (code "91") (name "Net-(U4-IN1)") (class "Default")
      (node (ref "R23") (pin "1") (pinfunction "1_1") (pintype "passive"))
      (node (ref "R27") (pin "2") (pinfunction "2_2") (pintype "passive"))
      (node (ref "U4") (pin "8") (pinfunction "IN1_8") (pintype "bidirectional"))
    )
    (net (code "92") (name "Net-(U4-IN2)") (class "Default")
      (node (ref "R24") (pin "1") (pinfunction "1_1") (pintype "passive"))
      (node (ref "R33") (pin "2") (pinfunction "2_2") (pintype "passive"))
      (node (ref "U4") (pin "4") (pinfunction "IN2_4") (pintype "bidirectional"))
    )
    (net (code "93") (name "Net-(U6A-+IN)") (class "Default")
      (node (ref "R42") (pin "1") (pinfunction "1_1") (pintype "passive"))
      (node (ref "R49") (pin "1") (pinfunction "1_1") (pintype "passive"))
      (node (ref "U6") (pin "3") (pinfunction "+IN_3") (pintype "input"))
    )
    (net (code "94") (name "Net-(U6A--IN)") (class "Default")
      (node (ref "C8") (pin "1") (pinfunction "1_1") (pintype "passive"))
      (node (ref "R36") (pin "1") (pinfunction "1_1") (pintype "passive"))
      (node (ref "R41") (pin "2") (pinfunction "2_2") (pintype "passive"))
      (node (ref "U6") (pin "2") (pinfunction "-IN_2") (pintype "input"))
    )
    (net (code "95") (name "Net-(U6B-+IN)") (class "Default")
      (node (ref "R56") (pin "1") (pinfunction "1_1") (pintype "passive"))
      (node (ref "R57") (pin "1") (pinfunction "1_1") (pintype "passive"))
      (node (ref "U6") (pin "5") (pinfunction "+IN_5") (pintype "input"))
    )
    (net (code "96") (name "Net-(U6B--IN)") (class "Default")
      (node (ref "C10") (pin "1") (pinfunction "1_1") (pintype "passive"))
      (node (ref "R50") (pin "1") (pinfunction "1_1") (pintype "passive"))
      (node (ref "R51") (pin "2") (pinfunction "2_2") (pintype "passive"))
      (node (ref "U6") (pin "6") (pinfunction "-IN_6") (pintype "input"))
    )
    (net (code "97") (name "Net-(U6C-+IN)") (class "Default")
      (node (ref "R60") (pin "1") (pinfunction "1_1") (pintype "passive"))
      (node (ref "R61") (pin "1") (pinfunction "1_1") (pintype "passive"))
      (node (ref "U6") (pin "10") (pinfunction "+IN_10") (pintype "input"))
    )
    (net (code "98") (name "Net-(U6C--IN)") (class "Default")
      (node (ref "C12") (pin "1") (pinfunction "1_1") (pintype "passive"))
      (node (ref "R58") (pin "1") (pinfunction "1_1") (pintype "passive"))
      (node (ref "R59") (pin "2") (pinfunction "2_2") (pintype "passive"))
      (node (ref "U6") (pin "9") (pinfunction "-IN_9") (pintype "input"))
    )
    (net (code "99") (name "Net-(U6D-+IN)") (class "Default")
      (node (ref "R34") (pin "1") (pinfunction "1_1") (pintype "passive"))
      (node (ref "R35") (pin "1") (pinfunction "1_1") (pintype "passive"))
      (node (ref "U6") (pin "12") (pinfunction "+IN_12") (pintype "input"))
    )
    (net (code "100") (name "Net-(U6D--IN)") (class "Default")
      (node (ref "C9") (pin "1") (pinfunction "1_1") (pintype "passive"))
      (node (ref "R68") (pin "1") (pinfunction "1_1") (pintype "passive"))
      (node (ref "R70") (pin "2") (pinfunction "2_2") (pintype "passive"))
      (node (ref "U6") (pin "13") (pinfunction "-IN_13") (pintype "input"))
    )
    (net (code "101") (name "Net-(U7-EN)") (class "Default")
      (node (ref "C59") (pin "1") (pinfunction "1_1") (pintype "passive"))
      (node (ref "FB4") (pin "2") (pinfunction "2_2") (pintype "passive"))
      (node (ref "U7") (pin "2") (pinfunction "VIN_2") (pintype "bidirectional"))
      (node (ref "U7") (pin "3") (pinfunction "EN_3") (pintype "bidirectional"))
    )
    (net (code "102") (name "Net-(U7-FB)") (class "Default")
      (node (ref "R87") (pin "1") (pinfunction "1_1") (pintype "passive"))
      (node (ref "R88") (pin "2") (pinfunction "2_2") (pintype "passive"))
      (node (ref "U7") (pin "5") (pinfunction "FB_5") (pintype "bidirectional"))
    )
    (net (code "103") (name "Net-(U7-SW)") (class "Default")
      (node (ref "L4") (pin "P$1") (pinfunction "P$1_P$1") (pintype "bidirectional"))
      (node (ref "U7") (pin "7") (pinfunction "SW_7") (pintype "bidirectional"))
    )
    (net (code "104") (name "Net-(U10A-+IN)") (class "Default")
      (node (ref "C19") (pin "2") (pinfunction "2_2") (pintype "passive"))
      (node (ref "R32") (pin "1") (pinfunction "1_1") (pintype "passive"))
      (node (ref "R38") (pin "2") (pinfunction "2_2") (pintype "passive"))
      (node (ref "U10") (pin "3") (pinfunction "+IN_3") (pintype "input"))
    )
    (net (code "105") (name "Net-(U10A--IN)") (class "Default")
      (node (ref "R69") (pin "2") (pinfunction "2_2") (pintype "passive"))
      (node (ref "U10") (pin "1") (pinfunction "OUT_1") (pintype "output"))
      (node (ref "U10") (pin "2") (pinfunction "-IN_2") (pintype "input"))
    )
    (net (code "106") (name "Net-(U10B-+IN)") (class "Default")
      (node (ref "C21") (pin "2") (pinfunction "2_2") (pintype "passive"))
      (node (ref "R44") (pin "1") (pinfunction "1_1") (pintype "passive"))
      (node (ref "R46") (pin "2") (pinfunction "2_2") (pintype "passive"))
      (node (ref "U10") (pin "5") (pinfunction "+IN_5") (pintype "input"))
    )
    (net (code "107") (name "Net-(U10B--IN)") (class "Default")
      (node (ref "R71") (pin "2") (pinfunction "2_2") (pintype "passive"))
      (node (ref "U10") (pin "6") (pinfunction "-IN_6") (pintype "input"))
      (node (ref "U10") (pin "7") (pinfunction "OUT_7") (pintype "output"))
    )
    (net (code "108") (name "Net-(U10C-+IN)") (class "Default")
      (node (ref "C24") (pin "2") (pinfunction "2_2") (pintype "passive"))
      (node (ref "R48") (pin "1") (pinfunction "1_1") (pintype "passive"))
      (node (ref "U10") (pin "10") (pinfunction "+IN_10") (pintype "input"))
    )
    (net (code "109") (name "Net-(U10D-+IN)") (class "Default")
      (node (ref "C25") (pin "2") (pinfunction "2_2") (pintype "passive"))
      (node (ref "R62") (pin "1") (pinfunction "1_1") (pintype "passive"))
      (node (ref "U10") (pin "12") (pinfunction "+IN_12") (pintype "input"))
    )
    (net (code "110") (name "Net-(U15-A)") (class "Default")
      (node (ref "D5") (pin "C") (pinfunction "C_C") (pintype "passive"))
      (node (ref "R63") (pin "1") (pinfunction "1_1") (pintype "passive"))
      (node (ref "U15") (pin "1") (pinfunction "A_1") (pintype "bidirectional"))
    )
    (net (code "111") (name "OLED_CMD") (class "Default")
      (node (ref "U1") (pin "10") (pinfunction "GPIO9(SPI1_MISO)_10") (pintype "bidirectional"))
      (node (ref "U1") (pin "B10") (pinfunction "GPIO9(SPI1_MISO)_B10") (pintype "bidirectional"))
      (node (ref "U8") (pin "6") (pinfunction "DC_6") (pintype "bidirectional"))
    )
    (net (code "112") (name "OLED_RESET") (class "Default")
      (node (ref "C15") (pin "2") (pinfunction "2_2") (pintype "passive"))
      (node (ref "R26") (pin "1") (pinfunction "1_1") (pintype "passive"))
      (node (ref "U8") (pin "5") (pinfunction "RES_5") (pintype "bidirectional"))
    )
    (net (code "113") (name "OUT_L_ATTEN") (class "Default")
      (node (ref "P1") (pin "7") (pinfunction "7_7") (pintype "passive"))
      (node (ref "P1") (pin "8") (pinfunction "8_8") (pintype "passive"))
      (node (ref "R5") (pin "1") (pinfunction "1_1") (pintype "passive"))
      (node (ref "R7") (pin "1") (pinfunction "1_1") (pintype "passive"))
    )
    (net (code "114") (name "OUT_R_ATTEN") (class "Default")
      (node (ref "P1") (pin "5") (pinfunction "5_5") (pintype "passive"))
      (node (ref "P1") (pin "6") (pinfunction "6_6") (pintype "passive"))
      (node (ref "R13") (pin "1") (pinfunction "1_1") (pintype "passive"))
      (node (ref "R20") (pin "1") (pinfunction "1_1") (pintype "passive"))
    )
    (net (code "115") (name "POT_1") (class "Default")
      (node (ref "U11") (pin "13") (pinfunction "X0_13") (pintype "bidirectional"))
      (node (ref "VR_1") (pin "2") (pinfunction "2_2") (pintype "passive"))
    )
    (net (code "116") (name "POT_2") (class "Default")
      (node (ref "U11") (pin "14") (pinfunction "X1_14") (pintype "bidirectional"))
      (node (ref "VR_3") (pin "2") (pinfunction "2_2") (pintype "passive"))
    )
    (net (code "117") (name "POT_3") (class "Default")
      (node (ref "U11") (pin "15") (pinfunction "X2_15") (pintype "bidirectional"))
      (node (ref "VR_5") (pin "2") (pinfunction "2_2") (pintype "passive"))
    )
    (net (code "118") (name "POT_4") (class "Default")
      (node (ref "U11") (pin "12") (pinfunction "X3_12") (pintype "bidirectional"))
      (node (ref "VR_2") (pin "2") (pinfunction "2_2") (pintype "passive"))
    )
    (net (code "119") (name "POT_5") (class "Default")
      (node (ref "U11") (pin "1") (pinfunction "X4_1") (pintype "bidirectional"))
      (node (ref "VR_4") (pin "2") (pinfunction "2_2") (pintype "passive"))
    )
    (net (code "120") (name "POT_6") (class "Default")
      (node (ref "U11") (pin "5") (pinfunction "X5_5") (pintype "bidirectional"))
      (node (ref "VR_6") (pin "2") (pinfunction "2_2") (pintype "passive"))
    )
    (net (code "121") (name "POT_7") (class "Default")
      (node (ref "U11") (pin "2") (pinfunction "X6_2") (pintype "bidirectional"))
      (node (ref "VR_7") (pin "2") (pinfunction "2_2") (pintype "passive"))
    )
    (net (code "122") (name "POT_8") (class "Default")
      (node (ref "U11") (pin "4") (pinfunction "X7_4") (pintype "bidirectional"))
      (node (ref "VR_8") (pin "2") (pinfunction "S_2") (pintype "passive"))
    )
    (net (code "123") (name "POT_MUX_ADC") (class "Default")
      (node (ref "U1") (pin "23") (pinfunction "GPIO16(ADC1)_23") (pintype "bidirectional"))
      (node (ref "U1") (pin "B23") (pinfunction "GPIO16(ADC1)_B23") (pintype "bidirectional"))
      (node (ref "U11") (pin "3") (pinfunction "X_3") (pintype "bidirectional"))
    )
    (net (code "124") (name "SD_CK") (class "Default")
      (node (ref "U1") (pin "7") (pinfunction "GPIO6(SDMMC1_CK)_7") (pintype "bidirectional"))
      (node (ref "U1") (pin "B7") (pinfunction "GPIO6(SDMMC1_CK)_B7") (pintype "bidirectional"))
      (node (ref "U2") (pin "P$5") (pinfunction "SCK_P$5") (pintype "bidirectional"))
    )
    (net (code "125") (name "SD_CMD") (class "Default")
      (node (ref "R1") (pin "1") (pinfunction "1_1") (pintype "passive"))
      (node (ref "U1") (pin "6") (pinfunction "GPIO5(SDMMC1_CMD)_6") (pintype "bidirectional"))
      (node (ref "U1") (pin "B6") (pinfunction "GPIO5(SDMMC1_CMD)_B6") (pintype "bidirectional"))
      (node (ref "U2") (pin "P$3") (pinfunction "CMD/DI_P$3") (pintype "bidirectional"))
    )
    (net (code "126") (name "SD_D0") (class "Default")
      (node (ref "R2") (pin "1") (pinfunction "1_1") (pintype "passive"))
      (node (ref "U1") (pin "5") (pinfunction "GPIO4(SDMMC1_D0)_5") (pintype "bidirectional"))
      (node (ref "U1") (pin "B5") (pinfunction "GPIO4(SDMMC1_D0)_B5") (pintype "bidirectional"))
      (node (ref "U2") (pin "P$7") (pinfunction "D0/DO_P$7") (pintype "bidirectional"))
    )
    (net (code "127") (name "SD_D1") (class "Default")
      (node (ref "R16") (pin "1") (pinfunction "1_1") (pintype "passive"))
      (node (ref "U1") (pin "4") (pinfunction "GPIO3(SDMMC1_D1)_4") (pintype "bidirectional"))
      (node (ref "U1") (pin "B4") (pinfunction "GPIO3(SDMMC1_D1)_B4") (pintype "bidirectional"))
      (node (ref "U2") (pin "P$8") (pinfunction "D1/RSV_P$8") (pintype "bidirectional"))
    )
    (net (code "128") (name "SD_D2") (class "Default")
      (node (ref "R3") (pin "1") (pinfunction "1_1") (pintype "passive"))
      (node (ref "U1") (pin "3") (pinfunction "GPIO2(SDMMC1_D2)_3") (pintype "bidirectional"))
      (node (ref "U1") (pin "B3") (pinfunction "GPIO2(SDMMC1_D2)_B3") (pintype "bidirectional"))
      (node (ref "U2") (pin "P$1") (pinfunction "D2/NC_P$1") (pintype "bidirectional"))
    )
    (net (code "129") (name "SD_D3") (class "Default")
      (node (ref "R4") (pin "1") (pinfunction "1_1") (pintype "passive"))
      (node (ref "U1") (pin "2") (pinfunction "GPIO1(SDMMC1_D3)_2") (pintype "bidirectional"))
      (node (ref "U1") (pin "B2") (pinfunction "GPIO1(SDMMC1_D3)_B2") (pintype "bidirectional"))
      (node (ref "U2") (pin "P$2") (pinfunction "D3/CS_P$2") (pintype "bidirectional"))
    )
    (net (code "130") (name "SPI1_CS") (class "Default")
      (node (ref "U1") (pin "8") (pinfunction "GPIO7(SPI1_NSS)_8") (pintype "bidirectional"))
      (node (ref "U1") (pin "B8") (pinfunction "GPIO7(SPI1_NSS)_B8") (pintype "bidirectional"))
      (node (ref "U8") (pin "7") (pinfunction "CS_7") (pintype "bidirectional"))
    )
    (net (code "131") (name "SPI1_MOSI") (class "Default")
      (node (ref "U1") (pin "11") (pinfunction "GPIO10(SPI1_MOSI)_11") (pintype "bidirectional"))
      (node (ref "U1") (pin "B11") (pinfunction "GPIO10(SPI1_MOSI)_B11") (pintype "bidirectional"))
      (node (ref "U8") (pin "4") (pinfunction "SDA_4") (pintype "bidirectional"))
    )
    (net (code "132") (name "SPI1_SCK") (class "Default")
      (node (ref "U1") (pin "9") (pinfunction "GPIO8(SPI1_SCK)_9") (pintype "bidirectional"))
      (node (ref "U1") (pin "B9") (pinfunction "GPIO8(SPI1_SCK)_B9") (pintype "bidirectional"))
      (node (ref "U8") (pin "3") (pinfunction "SCL_3") (pintype "bidirectional"))
    )
    (net (code "133") (name "TAC_SWITCH_1") (class "Default")
      (node (ref "S1") (pin "1") (pinfunction "1_1") (pintype "passive"))
      (node (ref "S1") (pin "2") (pinfunction "2_2") (pintype "passive"))
      (node (ref "U1") (pin "37") (pinfunction "GPIO30(USB_HS_D+)_37") (pintype "bidirectional"))
      (node (ref "U1") (pin "B37") (pinfunction "GPIO30(USB_HS_D+)_B37") (pintype "bidirectional"))
    )
    (net (code "134") (name "TAC_SWITCH_2") (class "Default")
      (node (ref "S2") (pin "1") (pinfunction "1_1") (pintype "passive"))
      (node (ref "S2") (pin "2") (pinfunction "2_2") (pintype "passive"))
      (node (ref "U1") (pin "36") (pinfunction "GPIO29(USB_HS_D_-)_36") (pintype "bidirectional"))
      (node (ref "U1") (pin "B36") (pinfunction "GPIO29(USB_HS_D_-)_B36") (pintype "bidirectional"))
    )
    (net (code "135") (name "USART1_RX") (class "Default")
      (node (ref "R64") (pin "2") (pinfunction "2_2") (pintype "passive"))
      (node (ref "U1") (pin "15") (pinfunction "GPIO14(USART1_RX)_15") (pintype "bidirectional"))
      (node (ref "U1") (pin "B15") (pinfunction "GPIO14(USART1_RX)_B15") (pintype "bidirectional"))
      (node (ref "U15") (pin "4") (pinfunction "OUT_4") (pintype "bidirectional"))
    )
    (net (code "136") (name "USART1_TX") (class "Default")
      (node (ref "R55") (pin "2") (pinfunction "2_2") (pintype "passive"))
      (node (ref "U1") (pin "14") (pinfunction "GPIO13(USART1_TX)_14") (pintype "bidirectional"))
      (node (ref "U1") (pin "B14") (pinfunction "GPIO13(USART1_TX)_B14") (pintype "bidirectional"))
    )
    (net (code "137") (name "V_AUDIOBIAS") (class "Default")
      (node (ref "R48") (pin "2") (pinfunction "2_2") (pintype "passive"))
      (node (ref "R62") (pin "2") (pinfunction "2_2") (pintype "passive"))
      (node (ref "U3") (pin "1") (pinfunction "OUT_1") (pintype "output"))
      (node (ref "U3") (pin "2") (pinfunction "-IN_2") (pintype "input"))
    )
    (net (code "138") (name "unconnected-(H1-MOUNT-PadB3,2)") (class "Default")
      (node (ref "H1") (pin "B3,2") (pinfunction "MOUNT_B3,2") (pintype "passive"))
    )
    (net (code "139") (name "unconnected-(H2-MOUNT-PadB3,2)") (class "Default")
      (node (ref "H2") (pin "B3,2") (pinfunction "MOUNT_B3,2") (pintype "passive"))
    )
    (net (code "140") (name "unconnected-(J7-SW-Pad2)") (class "Default")
      (node (ref "J7") (pin "2") (pinfunction "SW_2") (pintype "passive"))
    )
    (net (code "141") (name "unconnected-(J8-RING-Pad3)") (class "Default")
      (node (ref "J8") (pin "3") (pinfunction "RING_3") (pintype "passive"))
    )
    (net (code "142") (name "unconnected-(J8-RING_SW-Pad6)") (class "Default")
      (node (ref "J8") (pin "6") (pinfunction "RING_SW_6") (pintype "passive"))
    )
    (net (code "143") (name "unconnected-(J8-TIP_SW-Pad5)") (class "Default")
      (node (ref "J8") (pin "5") (pinfunction "TIP_SW_5") (pintype "passive"))
    )
    (net (code "144") (name "unconnected-(J9-RING-Pad3)") (class "Default")
      (node (ref "J9") (pin "3") (pinfunction "RING_3") (pintype "passive"))
    )
    (net (code "145") (name "unconnected-(J9-RING_SW-Pad6)") (class "Default")
      (node (ref "J9") (pin "6") (pinfunction "RING_SW_6") (pintype "passive"))
    )
    (net (code "146") (name "unconnected-(J10-RING_SW-Pad6)") (class "Default")
      (node (ref "J10") (pin "6") (pinfunction "RING_SW_6") (pintype "passive"))
    )
    (net (code "147") (name "unconnected-(J10-TIP_SW-Pad5)") (class "Default")
      (node (ref "J10") (pin "5") (pinfunction "TIP_SW_5") (pintype "passive"))
    )
    (net (code "148") (name "unconnected-(J12-RING-Pad3)") (class "Default")
      (node (ref "J12") (pin "3") (pinfunction "RING_3") (pintype "passive"))
    )
    (net (code "149") (name "unconnected-(J12-RING_SW-Pad6)") (class "Default")
      (node (ref "J12") (pin "6") (pinfunction "RING_SW_6") (pintype "passive"))
    )
    (net (code "150") (name "unconnected-(J12-TIP_SW-Pad5)") (class "Default")
      (node (ref "J12") (pin "5") (pinfunction "TIP_SW_5") (pintype "passive"))
    )
    (net (code "151") (name "unconnected-(J13-RING-Pad3)") (class "Default")
      (node (ref "J13") (pin "3") (pinfunction "RING_3") (pintype "passive"))
    )
    (net (code "152") (name "unconnected-(J13-RING_SW-Pad6)") (class "Default")
      (node (ref "J13") (pin "6") (pinfunction "RING_SW_6") (pintype "passive"))
    )
    (net (code "153") (name "unconnected-(J13-TIP_SW-Pad5)") (class "Default")
      (node (ref "J13") (pin "5") (pinfunction "TIP_SW_5") (pintype "passive"))
    )
    (net (code "154") (name "unconnected-(J_CV_OUT_1-PadNORM)") (class "Default")
      (node (ref "J_CV_OUT_1") (pin "NORM") (pinfunction "NORM_NORM") (pintype "passive"))
    )
    (net (code "155") (name "unconnected-(J_CV_OUT_2-PadNORM)") (class "Default")
      (node (ref "J_CV_OUT_2") (pin "NORM") (pinfunction "NORM_NORM") (pintype "passive"))
    )
    (net (code "156") (name "unconnected-(J_GATE_IN_1-PadNORM)") (class "Default")
      (node (ref "J_GATE_IN_1") (pin "NORM") (pinfunction "NORM_NORM") (pintype "passive"))
    )
    (net (code "157") (name "unconnected-(J_GATE_OUT-PadNORM)") (class "Default")
      (node (ref "J_GATE_OUT") (pin "NORM") (pinfunction "NORM_NORM") (pintype "passive"))
    )
    (net (code "158") (name "unconnected-(U5-LED8-Pad15)") (class "Default")
      (node (ref "U5") (pin "15") (pinfunction "LED8_15") (pintype "bidirectional"))
    )
    (net (code "159") (name "unconnected-(U5-LED9-Pad16)") (class "Default")
      (node (ref "U5") (pin "16") (pinfunction "LED9_16") (pintype "bidirectional"))
    )
    (net (code "160") (name "unconnected-(U5-LED10-Pad17)") (class "Default")
      (node (ref "U5") (pin "17") (pinfunction "LED10_17") (pintype "bidirectional"))
    )
    (net (code "161") (name "unconnected-(U5-LED11-Pad18)") (class "Default")
      (node (ref "U5") (pin "18") (pinfunction "LED11_18") (pintype "bidirectional"))
    )
    (net (code "162") (name "unconnected-(U5-LED12-Pad19)") (class "Default")
      (node (ref "U5") (pin "19") (pinfunction "LED12_19") (pintype "bidirectional"))
    )
    (net (code "163") (name "unconnected-(U5-LED13-Pad20)") (class "Default")
      (node (ref "U5") (pin "20") (pinfunction "LED13_20") (pintype "bidirectional"))
    )
    (net (code "164") (name "unconnected-(U5-LED14-Pad21)") (class "Default")
      (node (ref "U5") (pin "21") (pinfunction "LED14_21") (pintype "bidirectional"))
    )
    (net (code "165") (name "unconnected-(U5-LED15-Pad22)") (class "Default")
      (node (ref "U5") (pin "22") (pinfunction "LED15_22") (pintype "bidirectional"))
    )
    (net (code "166") (name "unconnected-(U7-PG-Pad8)") (class "Default")
      (node (ref "U7") (pin "8") (pinfunction "PG_8") (pintype "bidirectional"))
    )
    (net (code "167") (name "unconnected-(U16-CD4021_D2-Pad10A)") (class "Default")
      (node (ref "U16") (pin "10A") (pinfunction "CD4021_D2_10A") (pintype "bidirectional"))
    )
    (net (code "168") (name "unconnected-(U16-LED_B3_G-Pad8A)") (class "Default")
      (node (ref "U16") (pin "8A") (pinfunction "LED_B3_G_8A") (pintype "bidirectional"))
    )
    (net (code "169") (name "unconnected-(U16-LED_B3_R-Pad9A)") (class "Default")
      (node (ref "U16") (pin "9A") (pinfunction "LED_B3_R_9A") (pintype "bidirectional"))
    )
    (net (code "170") (name "unconnected-(U16-LED_B4_G-Pad2B)") (class "Default")
      (node (ref "U16") (pin "2B") (pinfunction "LED_B4_G_2B") (pintype "bidirectional"))
    )
    (net (code "171") (name "unconnected-(U16-LED_B4_R-Pad1B)") (class "Default")
      (node (ref "U16") (pin "1B") (pinfunction "LED_B4_R_1B") (pintype "bidirectional"))
    )
    (net (code "172") (name "unconnected-(U16-LED_B5_G-Pad4B)") (class "Default")
      (node (ref "U16") (pin "4B") (pinfunction "LED_B5_G_4B") (pintype "bidirectional"))
    )
    (net (code "173") (name "unconnected-(U16-LED_B5_R-Pad3B)") (class "Default")
      (node (ref "U16") (pin "3B") (pinfunction "LED_B5_R_3B") (pintype "bidirectional"))
    )
    (net (code "174") (name "unconnected-(U16-LED_B6_G-Pad6B)") (class "Default")
      (node (ref "U16") (pin "6B") (pinfunction "LED_B6_G_6B") (pintype "bidirectional"))
    )
    (net (code "175") (name "unconnected-(U16-LED_B6_R-Pad5B)") (class "Default")
      (node (ref "U16") (pin "5B") (pinfunction "LED_B6_R_5B") (pintype "bidirectional"))
    )
    (net (code "176") (name "unconnected-(U16-LED_B7_G-Pad7B)") (class "Default")
      (node (ref "U16") (pin "7B") (pinfunction "LED_B7_G_7B") (pintype "bidirectional"))
    )
    (net (code "177") (name "unconnected-(U16-LED_B7_R-Pad8B)") (class "Default")
      (node (ref "U16") (pin "8B") (pinfunction "LED_B7_R_8B") (pintype "bidirectional"))
    )
    (net (code "178") (name "unconnected-(U16-LED_B8_G-Pad9B)") (class "Default")
      (node (ref "U16") (pin "9B") (pinfunction "LED_B8_G_9B") (pintype "bidirectional"))
    )
    (net (code "179") (name "unconnected-(U16-LED_B8_R-Pad10B)") (class "Default")
      (node (ref "U16") (pin "10B") (pinfunction "LED_B8_R_10B") (pintype "bidirectional"))
    )
  )
)
